# Roland_memser.net
KiCad netlist of a schematic drawn in EAGLE
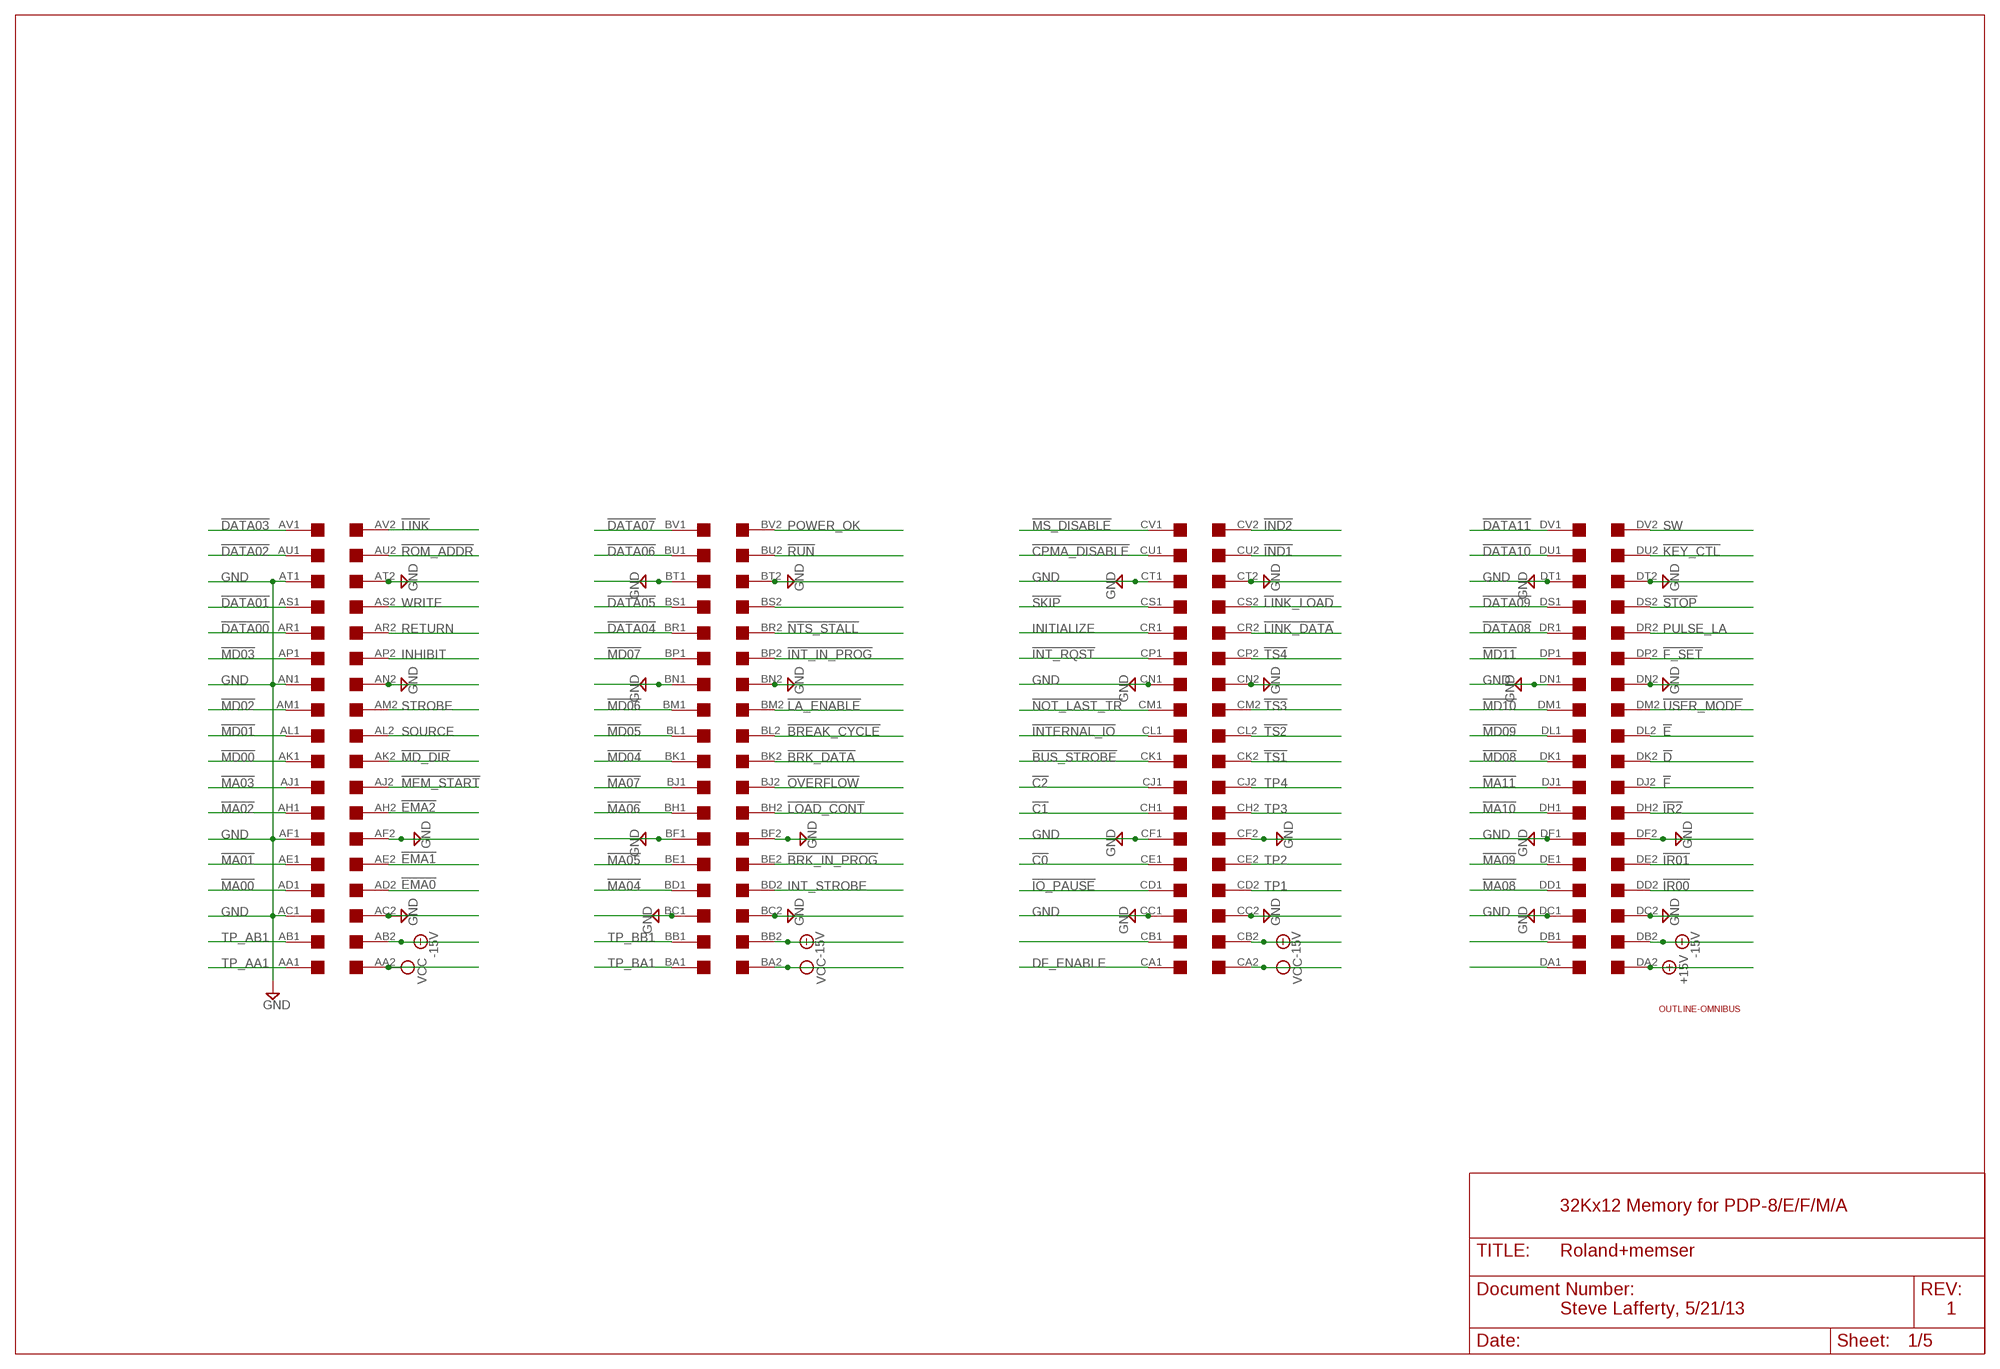
[diagram p0: schematic, sheet 1]
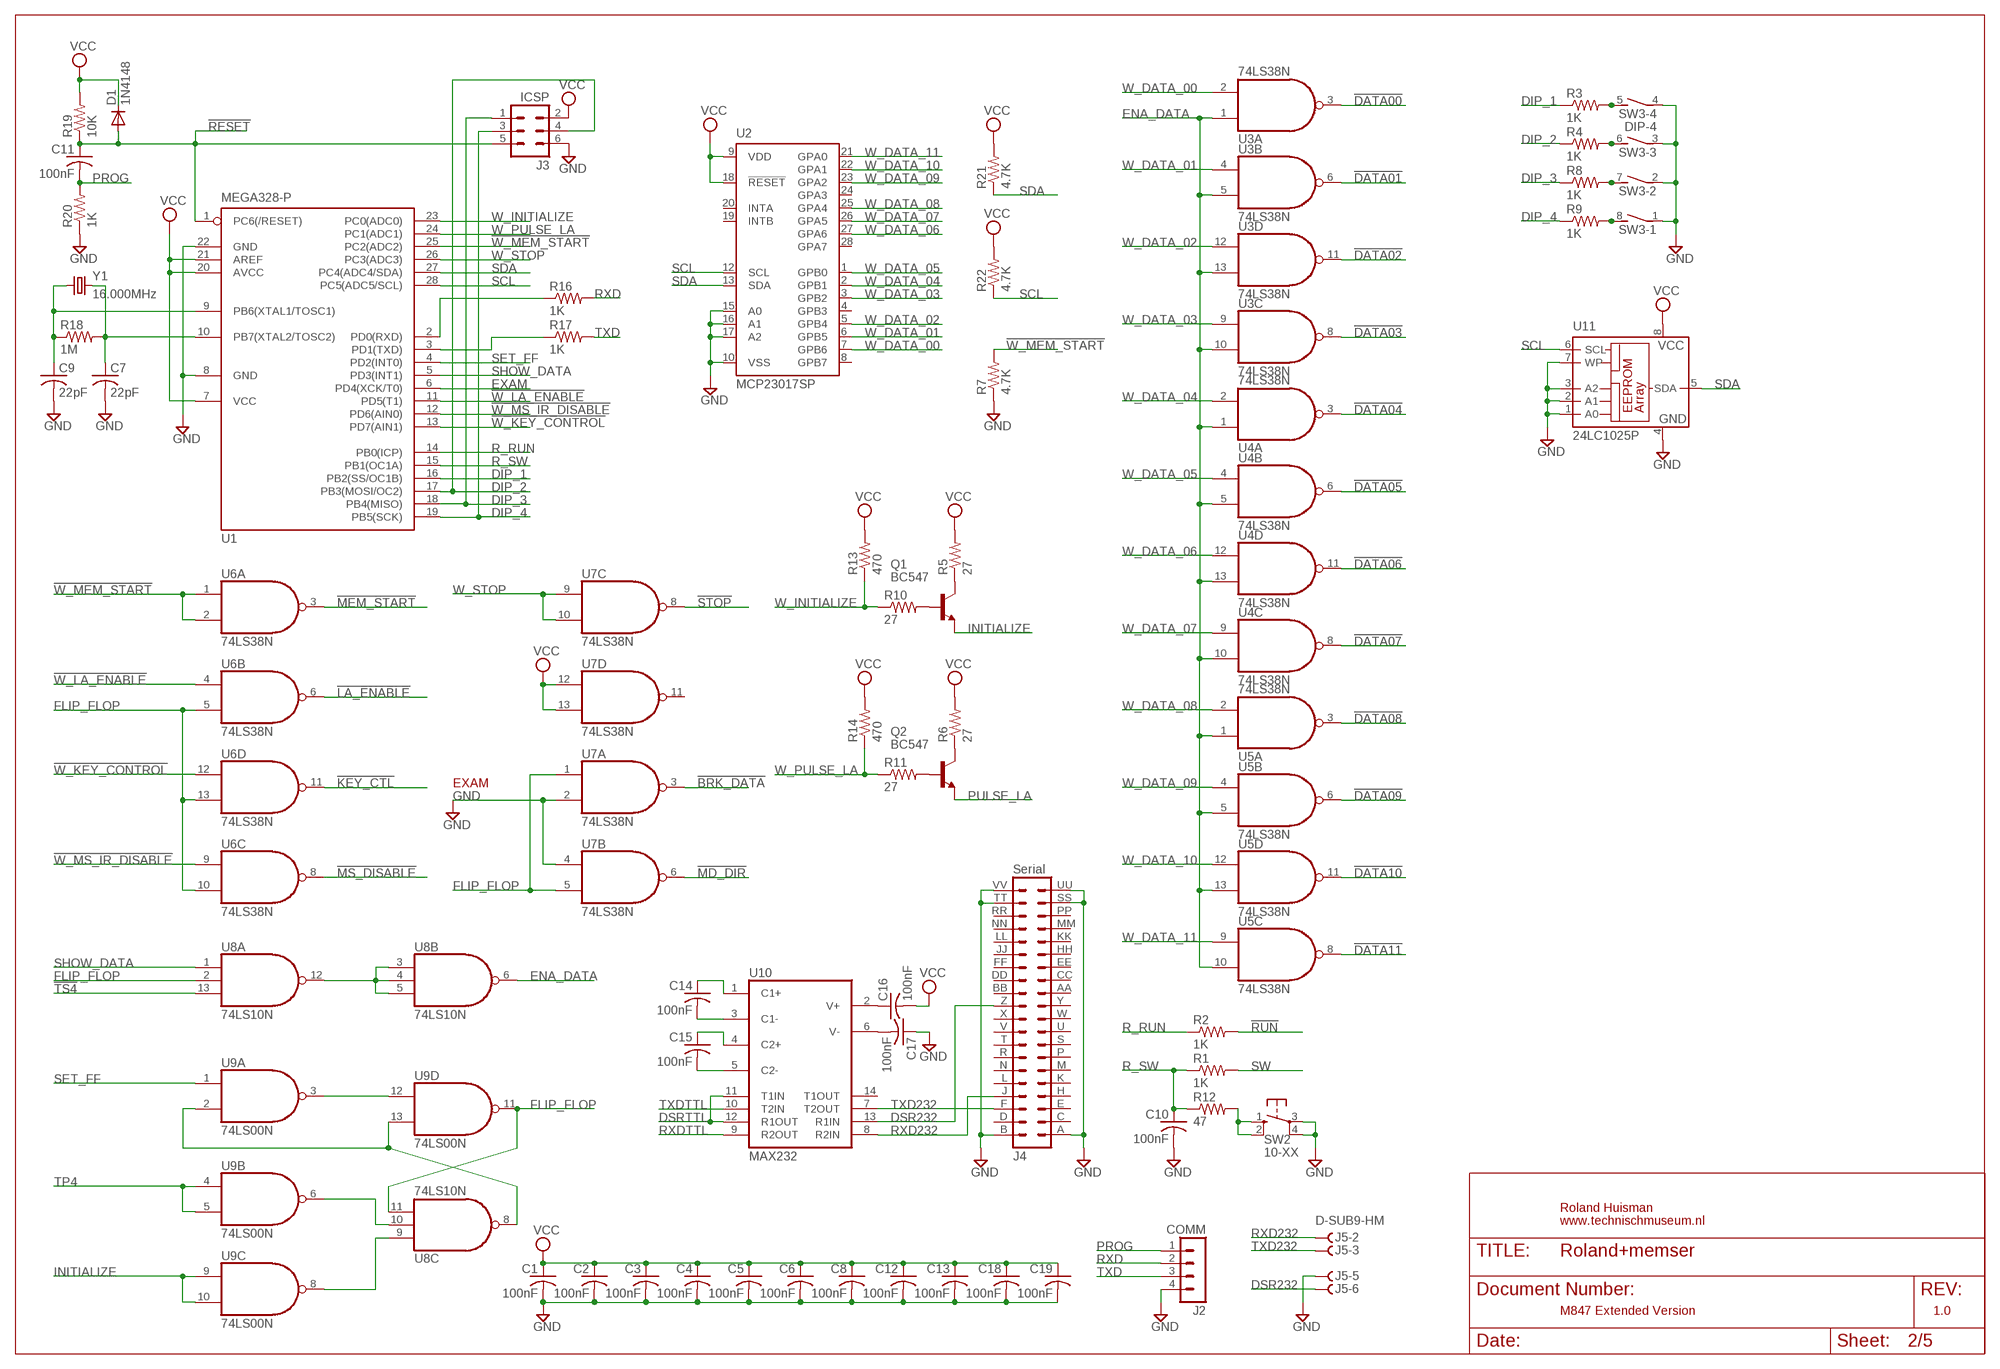
[diagram p1: schematic, sheet 2]
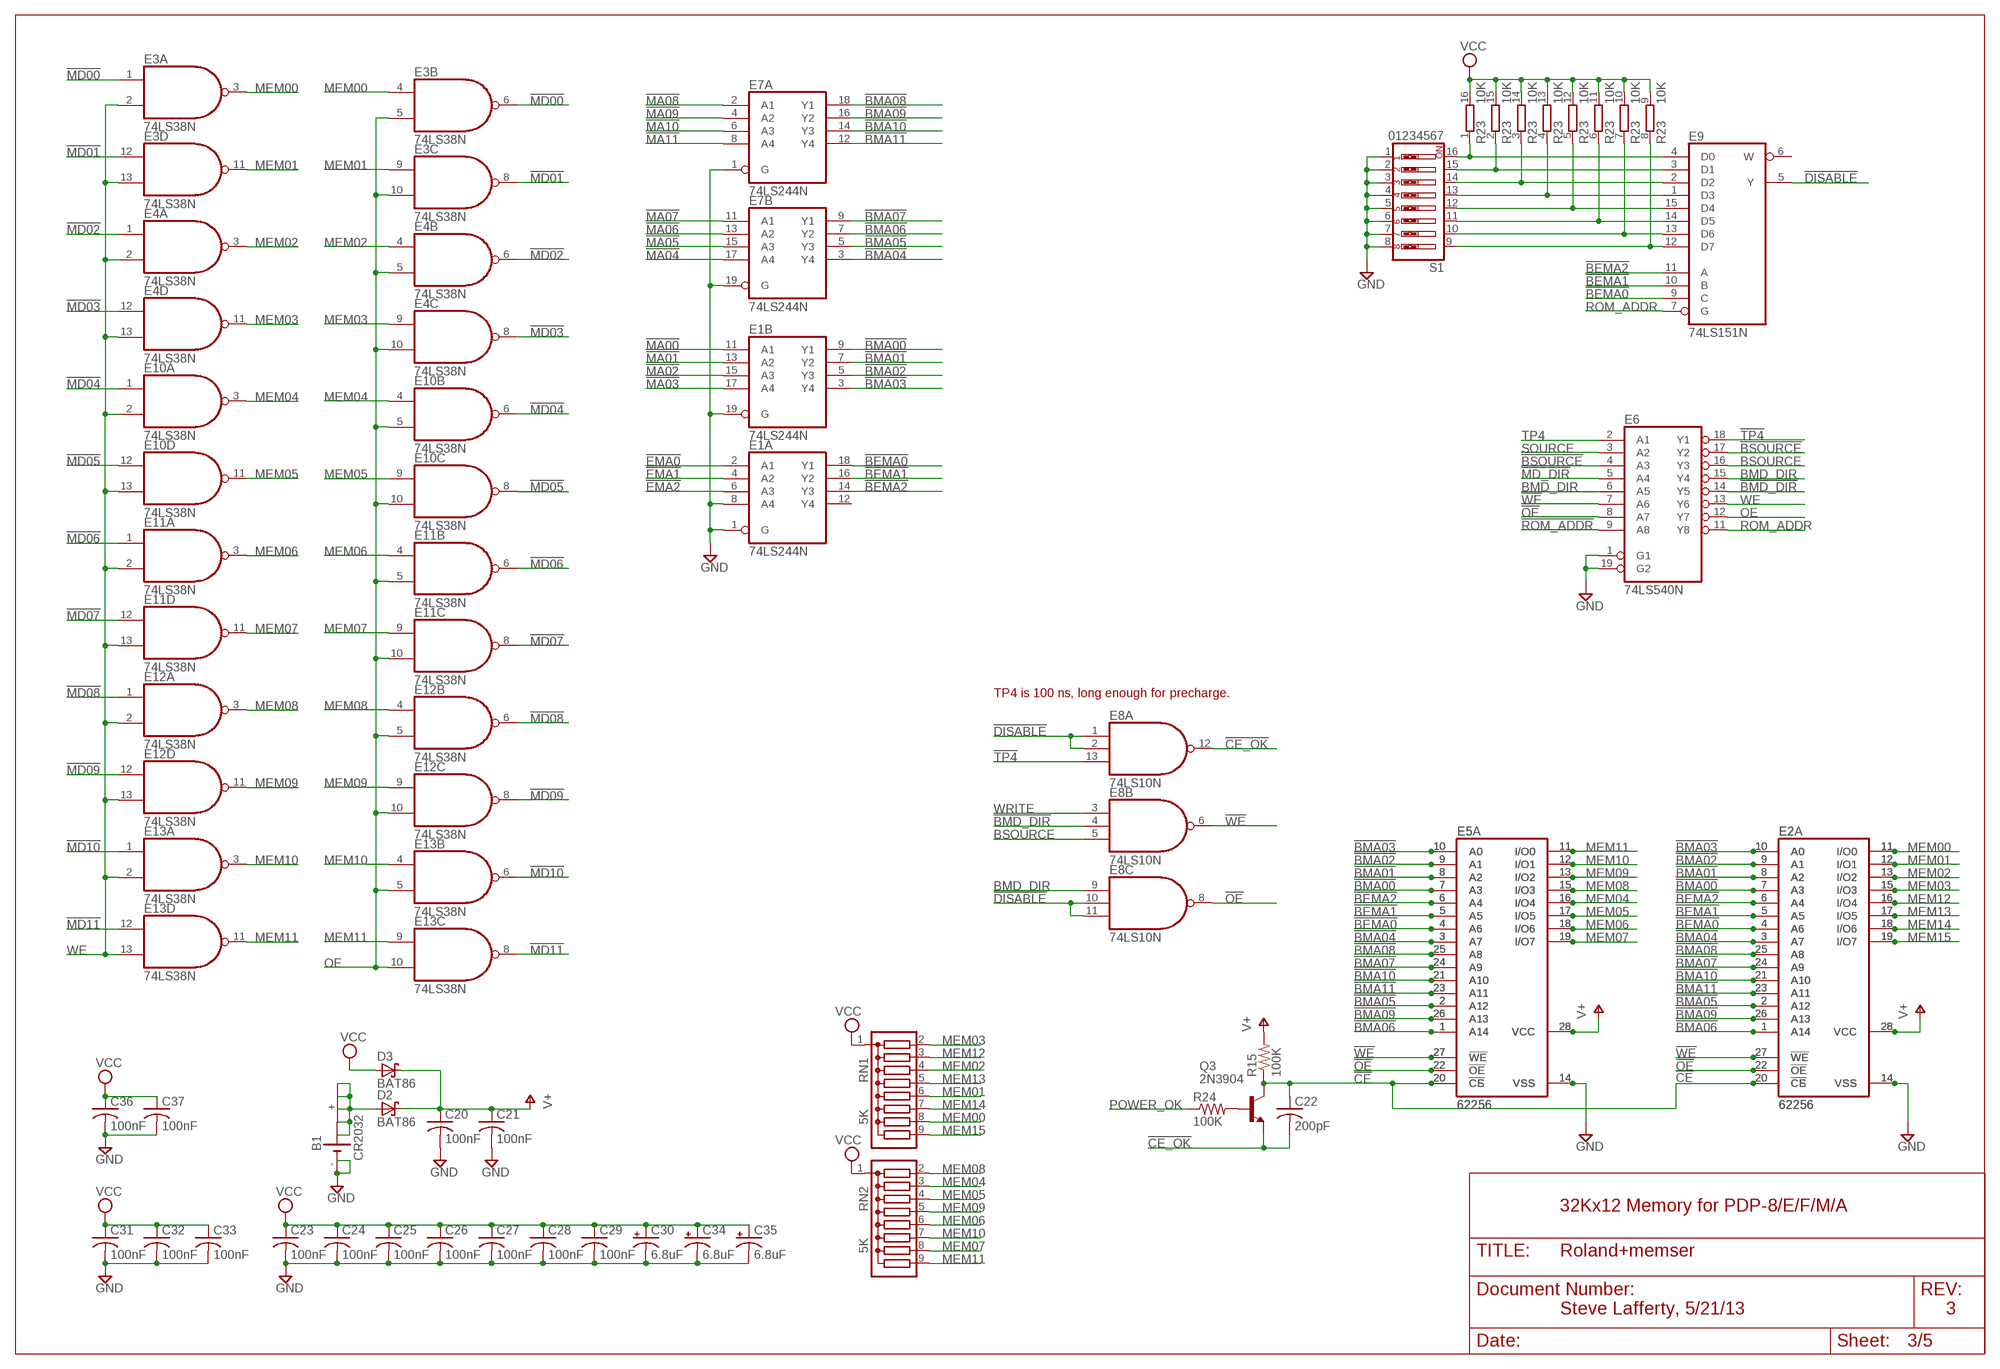
[diagram p2: schematic, sheet 3]
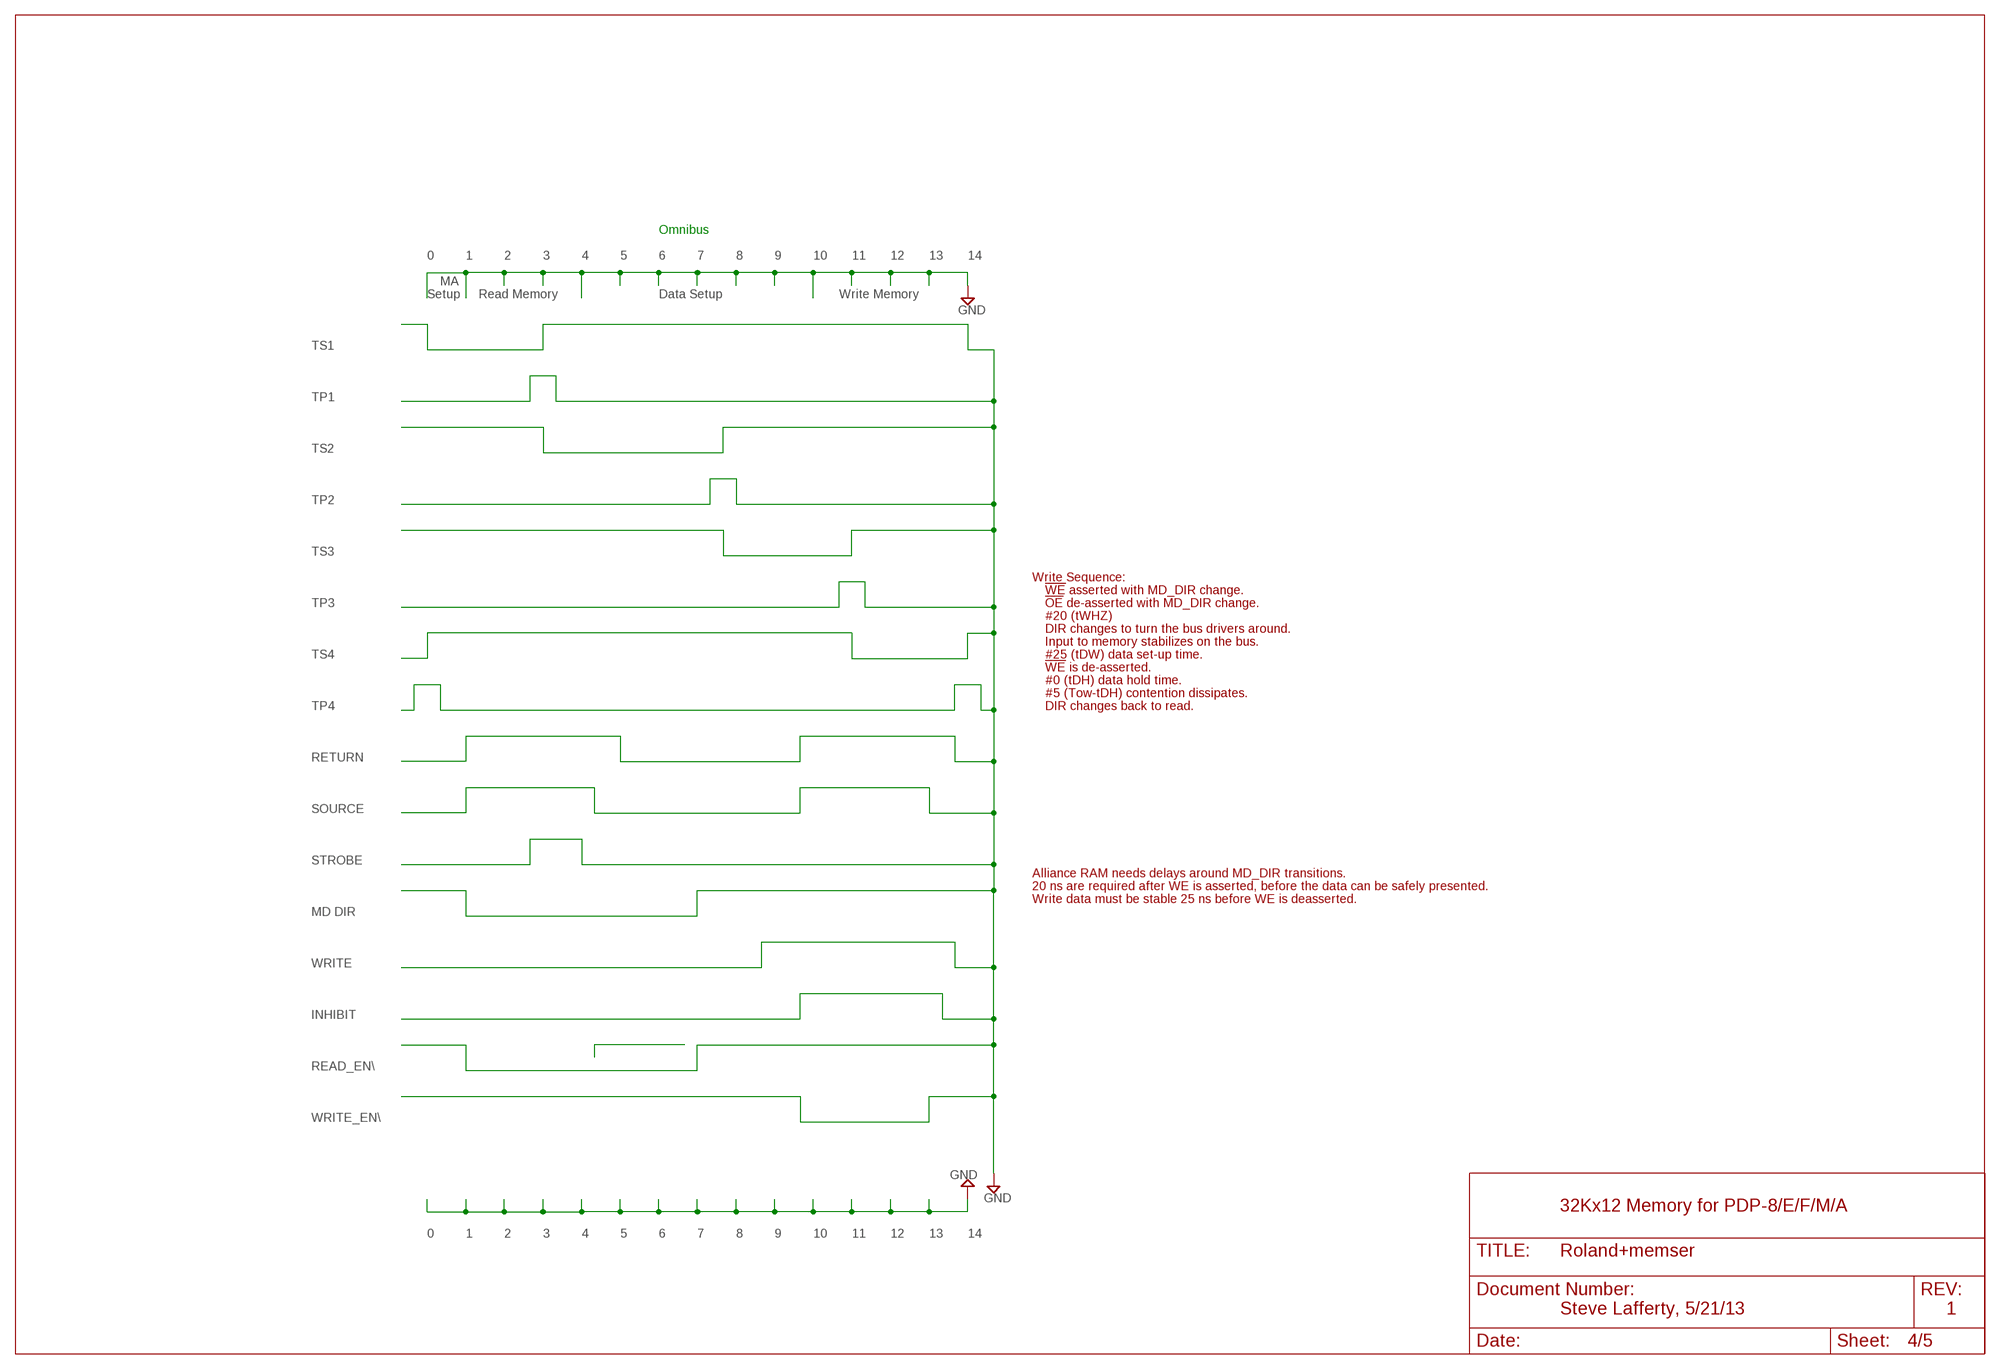
[diagram p3: schematic, sheet 4]
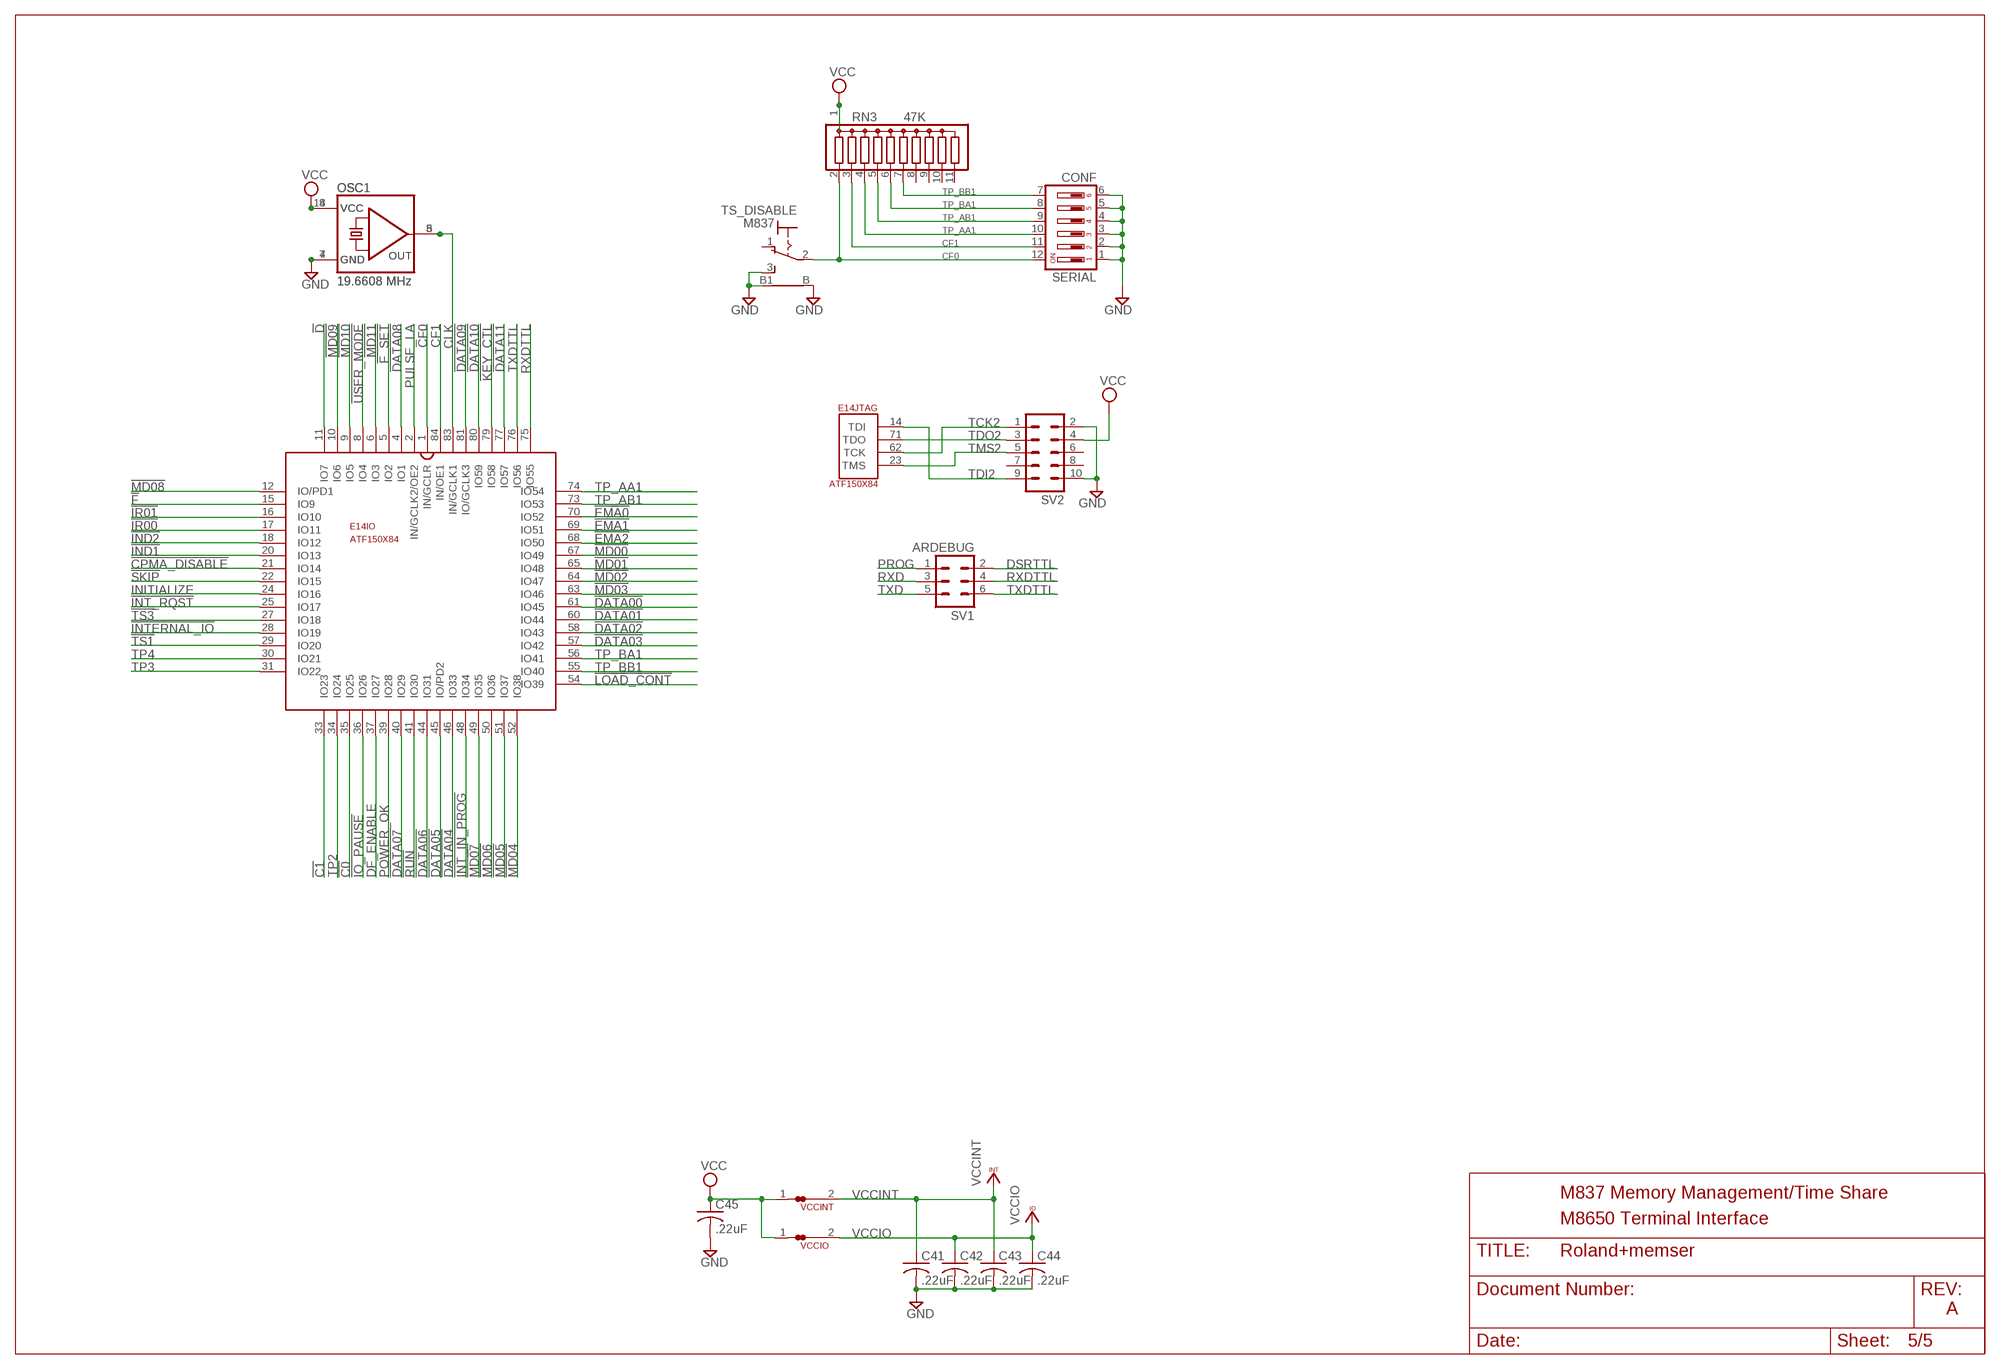
[diagram p4: schematic, sheet 5]

(export (version "E")
  (design (tool "Eeschema 10.0.6"))
  (components
    (comp (ref "J1")
      (value "EDGE")
      (footprint "eagle-import:EDGE-CON8")
      (libsource (lib "eagle-import") (part "QUAD"))
    )
    (comp (ref "U$1")
      (value "OUTLINE-OMNIBUS")
      (footprint "eagle-import:OMNIBUS")
      (libsource (lib "eagle-import") (part "OUTLINE-OMNIBUS"))
    )
    (comp (ref "C1")
      (value "100nF")
      (footprint "eagle-import:C050-025X075")
      (libsource (lib "eagle-import") (part "C-US050-025X075"))
    )
    (comp (ref "C2")
      (value "100nF")
      (footprint "eagle-import:C050-025X075")
      (libsource (lib "eagle-import") (part "C-US050-025X075"))
    )
    (comp (ref "C3")
      (value "100nF")
      (footprint "eagle-import:C050-025X075")
      (libsource (lib "eagle-import") (part "C-US050-025X075"))
    )
    (comp (ref "C4")
      (value "100nF")
      (footprint "eagle-import:C050-025X075")
      (libsource (lib "eagle-import") (part "C-US050-025X075"))
    )
    (comp (ref "C5")
      (value "100nF")
      (footprint "eagle-import:C050-025X075")
      (libsource (lib "eagle-import") (part "C-US050-025X075"))
    )
    (comp (ref "C6")
      (value "100nF")
      (footprint "eagle-import:C050-025X075")
      (libsource (lib "eagle-import") (part "C-US050-025X075"))
    )
    (comp (ref "C7")
      (value "22pF")
      (footprint "eagle-import:C050-025X075")
      (libsource (lib "eagle-import") (part "C-US050-025X075"))
    )
    (comp (ref "C8")
      (value "100nF")
      (footprint "eagle-import:C050-025X075")
      (libsource (lib "eagle-import") (part "C-US050-025X075"))
    )
    (comp (ref "C9")
      (value "22pF")
      (footprint "eagle-import:C050-025X075")
      (libsource (lib "eagle-import") (part "C-US050-025X075"))
    )
    (comp (ref "C10")
      (value "100nF")
      (footprint "eagle-import:C050-025X075")
      (libsource (lib "eagle-import") (part "C-US050-025X075"))
    )
    (comp (ref "C11")
      (value "100nF")
      (footprint "eagle-import:C050-025X075")
      (libsource (lib "eagle-import") (part "C-US050-025X075"))
    )
    (comp (ref "C12")
      (value "100nF")
      (footprint "eagle-import:C050-025X075")
      (libsource (lib "eagle-import") (part "C-US050-025X075"))
    )
    (comp (ref "C13")
      (value "100nF")
      (footprint "eagle-import:C050-025X075")
      (libsource (lib "eagle-import") (part "C-US050-025X075"))
    )
    (comp (ref "C14")
      (value "100nF")
      (footprint "eagle-import:C050-025X075")
      (libsource (lib "eagle-import") (part "C-US050-025X075"))
    )
    (comp (ref "C15")
      (value "100nF")
      (footprint "eagle-import:C050-025X075")
      (libsource (lib "eagle-import") (part "C-US050-025X075"))
    )
    (comp (ref "C16")
      (value "100nF")
      (footprint "eagle-import:C050-025X075")
      (libsource (lib "eagle-import") (part "C-US050-025X075"))
    )
    (comp (ref "C17")
      (value "100nF")
      (footprint "eagle-import:C050-025X075")
      (libsource (lib "eagle-import") (part "C-US050-025X075"))
    )
    (comp (ref "C18")
      (value "100nF")
      (footprint "eagle-import:C050-025X075")
      (libsource (lib "eagle-import") (part "C-US050-025X075"))
    )
    (comp (ref "C19")
      (value "100nF")
      (footprint "eagle-import:C050-025X075")
      (libsource (lib "eagle-import") (part "C-US050-025X075"))
    )
    (comp (ref "D1")
      (value "1N4148")
      (footprint "eagle-import:DO35-10")
      (libsource (lib "eagle-import") (part "1N4148DO35-10"))
    )
    (comp (ref "J2")
      (value "COMM")
      (footprint "eagle-import:MA04-1")
      (libsource (lib "eagle-import") (part "MA04-1"))
    )
    (comp (ref "J3")
      (value "ICSP")
      (footprint "eagle-import:MA03-2")
      (libsource (lib "eagle-import") (part "MA03-2"))
    )
    (comp (ref "J4")
      (value "Serial")
      (footprint "eagle-import:DEC40PINH")
      (libsource (lib "eagle-import") (part "DEC40PINH"))
    )
    (comp (ref "J5")
      (value "D-SUB9-HM")
      (footprint "eagle-import:H5M09RA")
      (libsource (lib "eagle-import") (part "D-SUB9-H5M09RA"))
    )
    (comp (ref "Q1")
      (value "BC547")
      (footprint "eagle-import:TO5")
      (libsource (lib "eagle-import") (part "-NPN-TO5"))
    )
    (comp (ref "Q2")
      (value "BC547")
      (footprint "eagle-import:TO5")
      (libsource (lib "eagle-import") (part "-NPN-TO5"))
    )
    (comp (ref "R1")
      (value "1K")
      (footprint "eagle-import:0207_10")
      (libsource (lib "eagle-import") (part "R-US_0207/10"))
    )
    (comp (ref "R2")
      (value "1K")
      (footprint "eagle-import:0207_10")
      (libsource (lib "eagle-import") (part "R-US_0207/10"))
    )
    (comp (ref "R3")
      (value "1K")
      (footprint "eagle-import:0207_10")
      (libsource (lib "eagle-import") (part "R-US_0207/10"))
    )
    (comp (ref "R4")
      (value "1K")
      (footprint "eagle-import:0207_10")
      (libsource (lib "eagle-import") (part "R-US_0207/10"))
    )
    (comp (ref "R5")
      (value "27")
      (footprint "eagle-import:0207_10")
      (libsource (lib "eagle-import") (part "R-US_0207/10"))
    )
    (comp (ref "R6")
      (value "27")
      (footprint "eagle-import:0207_10")
      (libsource (lib "eagle-import") (part "R-US_0207/10"))
    )
    (comp (ref "R7")
      (value "4.7K")
      (footprint "eagle-import:0207_10")
      (libsource (lib "eagle-import") (part "R-US_0207/10"))
    )
    (comp (ref "R8")
      (value "1K")
      (footprint "eagle-import:0207_10")
      (libsource (lib "eagle-import") (part "R-US_0207/10"))
    )
    (comp (ref "R9")
      (value "1K")
      (footprint "eagle-import:0207_10")
      (libsource (lib "eagle-import") (part "R-US_0207/10"))
    )
    (comp (ref "R10")
      (value "27")
      (footprint "eagle-import:0207_10")
      (libsource (lib "eagle-import") (part "R-US_0207/10"))
    )
    (comp (ref "R11")
      (value "27")
      (footprint "eagle-import:0207_10")
      (libsource (lib "eagle-import") (part "R-US_0207/10"))
    )
    (comp (ref "R12")
      (value "47")
      (footprint "eagle-import:0207_10")
      (libsource (lib "eagle-import") (part "R-US_0207/10"))
    )
    (comp (ref "R13")
      (value "470")
      (footprint "eagle-import:0207_10")
      (libsource (lib "eagle-import") (part "R-US_0207/10"))
    )
    (comp (ref "R14")
      (value "470")
      (footprint "eagle-import:0207_10")
      (libsource (lib "eagle-import") (part "R-US_0207/10"))
    )
    (comp (ref "R16")
      (value "1K")
      (footprint "eagle-import:0207_10")
      (libsource (lib "eagle-import") (part "R-US_0207/10"))
    )
    (comp (ref "R17")
      (value "1K")
      (footprint "eagle-import:0207_10")
      (libsource (lib "eagle-import") (part "R-US_0207/10"))
    )
    (comp (ref "R18")
      (value "1M")
      (footprint "eagle-import:0207_10")
      (libsource (lib "eagle-import") (part "R-US_0207/10"))
    )
    (comp (ref "R19")
      (value "10K")
      (footprint "eagle-import:0207_10")
      (libsource (lib "eagle-import") (part "R-US_0207/10"))
    )
    (comp (ref "R20")
      (value "1K")
      (footprint "eagle-import:0207_10")
      (libsource (lib "eagle-import") (part "R-US_0207/10"))
    )
    (comp (ref "R21")
      (value "4.7K")
      (footprint "eagle-import:0207_10")
      (libsource (lib "eagle-import") (part "R-US_0207/10"))
    )
    (comp (ref "R22")
      (value "4.7K")
      (footprint "eagle-import:0207_10")
      (libsource (lib "eagle-import") (part "R-US_0207/10"))
    )
    (comp (ref "SW2")
      (value "10-XX")
      (footprint "eagle-import:B3F-10XX")
      (fields (field (name "MPN") "B3F-1000"))
      (libsource (lib "eagle-import") (part "10-XX"))
    )
    (comp (ref "SW3")
      (value "DIP-4")
      (footprint "eagle-import:DIP04S")
      (libsource (lib "eagle-import") (part "DIP04S"))
    )
    (comp (ref "U1")
      (value "MEGA328-P")
      (footprint "eagle-import:DIL28-3")
      (libsource (lib "eagle-import") (part "MEGA8-P"))
    )
    (comp (ref "U2")
      (value "MCP23017SP")
      (footprint "eagle-import:DIL28-3")
      (fields (field (name "MF") "MICROCHIP") (field (name "MPN") "MCP23017-E/SP"))
      (libsource (lib "eagle-import") (part "MCP23017SP"))
    )
    (comp (ref "U3")
      (value "74LS38N")
      (footprint "eagle-import:DIL14")
      (libsource (lib "eagle-import") (part "7438NLS"))
    )
    (comp (ref "U4")
      (value "74LS38N")
      (footprint "eagle-import:DIL14")
      (libsource (lib "eagle-import") (part "7438NLS"))
    )
    (comp (ref "U5")
      (value "74LS38N")
      (footprint "eagle-import:DIL14")
      (libsource (lib "eagle-import") (part "7438NLS"))
    )
    (comp (ref "U6")
      (value "74LS38N")
      (footprint "eagle-import:DIL14")
      (libsource (lib "eagle-import") (part "7438NLS"))
    )
    (comp (ref "U7")
      (value "74LS38N")
      (footprint "eagle-import:DIL14")
      (libsource (lib "eagle-import") (part "7438NLS"))
    )
    (comp (ref "U8")
      (value "74LS10N")
      (footprint "eagle-import:DIL14")
      (libsource (lib "eagle-import") (part "7410NLS"))
    )
    (comp (ref "U9")
      (value "74LS00N")
      (footprint "eagle-import:DIL14")
      (libsource (lib "eagle-import") (part "7400NLS"))
    )
    (comp (ref "U10")
      (value "MAX232")
      (footprint "eagle-import:DIL16")
      (fields (field (name "MF") "MAXIM") (field (name "MPN") "MAX232ACPE+"))
      (libsource (lib "eagle-import") (part "MAX232"))
    )
    (comp (ref "U11")
      (value "24LC1025P")
      (footprint "eagle-import:DIL8")
      (fields (field (name "MF") "MICROCHIP") (field (name "MPN") "24LC025-I/P"))
      (libsource (lib "eagle-import") (part "24PLC025"))
    )
    (comp (ref "Y1")
      (value "16.000MHz")
      (footprint "eagle-import:HC49U-H")
      (libsource (lib "eagle-import") (part "CRYSTALHC49U-H"))
    )
    (comp (ref "C41")
      (value ".22uF")
      (footprint "eagle-import:C063-025X075")
      (libsource (lib "eagle-import") (part "C-US"))
    )
    (comp (ref "C42")
      (value ".22uF")
      (footprint "eagle-import:C063-025X075")
      (libsource (lib "eagle-import") (part "C-US"))
    )
    (comp (ref "C43")
      (value ".22uF")
      (footprint "eagle-import:C063-025X075")
      (libsource (lib "eagle-import") (part "C-US"))
    )
    (comp (ref "C44")
      (value ".22uF")
      (footprint "eagle-import:C063-025X075")
      (libsource (lib "eagle-import") (part "C-US"))
    )
    (comp (ref "C45")
      (value ".22uF")
      (footprint "eagle-import:C063-025X075")
      (libsource (lib "eagle-import") (part "C-US"))
    )
    (comp (ref "E14")
      (value "ATF150X84")
      (footprint "eagle-import:S84")
      (libsource (lib "eagle-import") (part "ATF150X84"))
    )
    (comp (ref "OSC")
      (value "19.6608 MHz")
      (footprint "eagle-import:DIL08S")
      (libsource (lib "eagle-import") (part "QG5460"))
    )
    (comp (ref "OSC1")
      (value "19.6608 MHz")
      (footprint "eagle-import:DIL14S")
      (libsource (lib "eagle-import") (part "QG5860"))
    )
    (comp (ref "RN3")
      (value "47K")
      (footprint "eagle-import:SIL11")
      (libsource (lib "eagle-import") (part "G10R"))
    )
    (comp (ref "SERIAL")
      (value "CONF")
      (footprint "eagle-import:DP-06")
      (fields (field (name "MPN") "MCDP06"))
      (libsource (lib "eagle-import") (part "DP06"))
    )
    (comp (ref "SV1")
      (value "ARDEBUG")
      (footprint "eagle-import:MA03-2")
      (libsource (lib "eagle-import") (part "MA03-2"))
    )
    (comp (ref "SV2")
      (value "ML10")
      (footprint "eagle-import:ML10")
      (libsource (lib "eagle-import") (part "ML10"))
    )
    (comp (ref "TS_DISABLE")
      (value "M837")
      (footprint "eagle-import:9070-1W")
      (libsource (lib "eagle-import") (part "9070-1W"))
    )
    (comp (ref "VCCINT")
      (value "JUMPER-NC1")
      (footprint "eagle-import:NC1")
      (libsource (lib "eagle-import") (part "JUMPER-NC1"))
    )
    (comp (ref "VCCIO")
      (value "JUMPER-NC1")
      (footprint "eagle-import:NC1")
      (libsource (lib "eagle-import") (part "JUMPER-NC1"))
    )
    (comp (ref "B1")
      (value "CR2032")
      (footprint "eagle-import:B2430UNI")
      (libsource (lib "eagle-import") (part "B2430UNI"))
    )
    (comp (ref "C20")
      (value "100nF")
      (footprint "eagle-import:C050-025X075")
      (libsource (lib "eagle-import") (part "C-US050-025X075"))
    )
    (comp (ref "C21")
      (value "100nF")
      (footprint "eagle-import:C050-025X075")
      (libsource (lib "eagle-import") (part "C-US050-025X075"))
    )
    (comp (ref "C22")
      (value "200pF")
      (footprint "eagle-import:C050-025X075")
      (libsource (lib "eagle-import") (part "C-US050-025X075"))
    )
    (comp (ref "C23")
      (value "100nF")
      (footprint "eagle-import:C050-025X075")
      (libsource (lib "eagle-import") (part "C-US050-025X075"))
    )
    (comp (ref "C24")
      (value "100nF")
      (footprint "eagle-import:C050-025X075")
      (libsource (lib "eagle-import") (part "C-US050-025X075"))
    )
    (comp (ref "C25")
      (value "100nF")
      (footprint "eagle-import:C050-025X075")
      (libsource (lib "eagle-import") (part "C-US050-025X075"))
    )
    (comp (ref "C26")
      (value "100nF")
      (footprint "eagle-import:C050-025X075")
      (libsource (lib "eagle-import") (part "C-US050-025X075"))
    )
    (comp (ref "C27")
      (value "100nF")
      (footprint "eagle-import:C050-025X075")
      (libsource (lib "eagle-import") (part "C-US050-025X075"))
    )
    (comp (ref "C28")
      (value "100nF")
      (footprint "eagle-import:C050-025X075")
      (libsource (lib "eagle-import") (part "C-US050-025X075"))
    )
    (comp (ref "C29")
      (value "100nF")
      (footprint "eagle-import:C050-025X075")
      (libsource (lib "eagle-import") (part "C-US050-025X075"))
    )
    (comp (ref "C30")
      (value "6.8uF")
      (footprint "eagle-import:E12-8")
      (libsource (lib "eagle-import") (part "CPOL-USE20-8AXIAL"))
    )
    (comp (ref "C31")
      (value "100nF")
      (footprint "eagle-import:C050-025X075")
      (libsource (lib "eagle-import") (part "C-US050-025X075"))
    )
    (comp (ref "C32")
      (value "100nF")
      (footprint "eagle-import:C050-025X075")
      (libsource (lib "eagle-import") (part "C-US050-025X075"))
    )
    (comp (ref "C33")
      (value "100nF")
      (footprint "eagle-import:C050-025X075")
      (libsource (lib "eagle-import") (part "C-US050-025X075"))
    )
    (comp (ref "C34")
      (value "6.8uF")
      (footprint "eagle-import:E12-8")
      (libsource (lib "eagle-import") (part "CPOL-USE20-8AXIAL"))
    )
    (comp (ref "C35")
      (value "6.8uF")
      (footprint "eagle-import:E12-8")
      (libsource (lib "eagle-import") (part "CPOL-USE20-8AXIAL"))
    )
    (comp (ref "C36")
      (value "100nF")
      (footprint "eagle-import:C050-025X075")
      (libsource (lib "eagle-import") (part "C-US050-025X075"))
    )
    (comp (ref "C37")
      (value "100nF")
      (footprint "eagle-import:C050-025X075")
      (libsource (lib "eagle-import") (part "C-US050-025X075"))
    )
    (comp (ref "D2")
      (value "BAT86")
      (footprint "eagle-import:DO35-10")
      (libsource (lib "eagle-import") (part "BAT19"))
    )
    (comp (ref "D3")
      (value "BAT86")
      (footprint "eagle-import:DO35-10")
      (libsource (lib "eagle-import") (part "BAT19"))
    )
    (comp (ref "E1")
      (value "74LS244N")
      (footprint "eagle-import:DIL20")
      (libsource (lib "eagle-import") (part "74244NLS"))
    )
    (comp (ref "E2")
      (value "62256")
      (footprint "eagle-import:DIL28-6")
      (libsource (lib "eagle-import") (part "58C256P"))
    )
    (comp (ref "E2A")
      (value "62256")
      (footprint "eagle-import:DIL28-3")
      (libsource (lib "eagle-import") (part "62832P"))
    )
    (comp (ref "E3")
      (value "74LS38N")
      (footprint "eagle-import:DIL14")
      (libsource (lib "eagle-import") (part "7438NLS"))
    )
    (comp (ref "E4")
      (value "74LS38N")
      (footprint "eagle-import:DIL14")
      (libsource (lib "eagle-import") (part "7438NLS"))
    )
    (comp (ref "E5")
      (value "62256")
      (footprint "eagle-import:DIL28-6")
      (libsource (lib "eagle-import") (part "58C256P"))
    )
    (comp (ref "E5A")
      (value "62256")
      (footprint "eagle-import:DIL28-3")
      (libsource (lib "eagle-import") (part "62832P"))
    )
    (comp (ref "E6")
      (value "74LS540N")
      (footprint "eagle-import:DIL20")
      (libsource (lib "eagle-import") (part "74540NLS"))
    )
    (comp (ref "E7")
      (value "74LS244N")
      (footprint "eagle-import:DIL20")
      (libsource (lib "eagle-import") (part "74244NLS"))
    )
    (comp (ref "E8")
      (value "74LS10N")
      (footprint "eagle-import:DIL14")
      (libsource (lib "eagle-import") (part "7410NLS"))
    )
    (comp (ref "E9")
      (value "74LS151N")
      (footprint "eagle-import:DIL16")
      (libsource (lib "eagle-import") (part "74151NLS"))
    )
    (comp (ref "E10")
      (value "74LS38N")
      (footprint "eagle-import:DIL14")
      (libsource (lib "eagle-import") (part "7438NLS"))
    )
    (comp (ref "E11")
      (value "74LS38N")
      (footprint "eagle-import:DIL14")
      (libsource (lib "eagle-import") (part "7438NLS"))
    )
    (comp (ref "E12")
      (value "74LS38N")
      (footprint "eagle-import:DIL14")
      (libsource (lib "eagle-import") (part "7438NLS"))
    )
    (comp (ref "E13")
      (value "74LS38N")
      (footprint "eagle-import:DIL14")
      (libsource (lib "eagle-import") (part "7438NLS"))
    )
    (comp (ref "Q3")
      (value "2N3904")
      (footprint "eagle-import:TO92")
      (libsource (lib "eagle-import") (part "2N3904"))
    )
    (comp (ref "R15")
      (value "100K")
      (footprint "eagle-import:0207_10")
      (libsource (lib "eagle-import") (part "R-US_0207/10"))
    )
    (comp (ref "R23")
      (value "10K")
      (footprint "eagle-import:DIL16")
      (libsource (lib "eagle-import") (part "8R-P"))
    )
    (comp (ref "R24")
      (value "100K")
      (footprint "eagle-import:0207_10")
      (libsource (lib "eagle-import") (part "R-US_0207/10"))
    )
    (comp (ref "RN1")
      (value "5K")
      (footprint "eagle-import:SIL9")
      (libsource (lib "eagle-import") (part "G08R"))
    )
    (comp (ref "RN2")
      (value "5K")
      (footprint "eagle-import:SIL9")
      (libsource (lib "eagle-import") (part "G08R"))
    )
    (comp (ref "S1")
      (value "01234567")
      (footprint "eagle-import:EDG-08")
      (libsource (lib "eagle-import") (part "SW_DIP-8"))
    )
  )
  (nets
    (net (code "1") (name "+15V") (class "Default")
      (node (ref "J1") (pin "DA2") (pinfunction "1_DA2") (pintype "bidirectional"))
    )
    (net (code "2") (name "-15V") (class "Default")
      (node (ref "J1") (pin "AB2") (pinfunction "1_AB2") (pintype "bidirectional"))
      (node (ref "J1") (pin "BB2") (pinfunction "1_BB2") (pintype "bidirectional"))
      (node (ref "J1") (pin "CB2") (pinfunction "1_CB2") (pintype "bidirectional"))
      (node (ref "J1") (pin "DB2") (pinfunction "1_DB2") (pintype "bidirectional"))
    )
    (net (code "3") (name "BMD_DIR") (class "Default")
      (node (ref "E6") (pin "15") (pinfunction "Y4_15") (pintype "tri_state"))
      (node (ref "E6") (pin "6") (pinfunction "A5_6") (pintype "input"))
      (node (ref "E8") (pin "9") (pinfunction "I0_9") (pintype "input"))
    )
    (net (code "4") (name "BSOURCE") (class "Default")
      (node (ref "E6") (pin "16") (pinfunction "Y3_16") (pintype "tri_state"))
      (node (ref "E8") (pin "5") (pinfunction "I2_5") (pintype "input"))
    )
    (net (code "5") (name "CF0") (class "Default")
      (node (ref "E14") (pin "1") (pinfunction "IN/GCLR_1") (pintype "input"))
      (node (ref "RN3") (pin "2") (pinfunction "2_2") (pintype "passive"))
      (node (ref "SERIAL") (pin "12") (pinfunction "12_12") (pintype "passive"))
      (node (ref "TS_DISABLE") (pin "2") (pinfunction "P_2") (pintype "passive"))
    )
    (net (code "6") (name "CF1") (class "Default")
      (node (ref "E14") (pin "84") (pinfunction "IN/OE1_84") (pintype "input"))
      (node (ref "RN3") (pin "3") (pinfunction "3_3") (pintype "passive"))
      (node (ref "SERIAL") (pin "11") (pinfunction "11_11") (pintype "passive"))
    )
    (net (code "7") (name "CLK") (class "Default")
      (node (ref "E14") (pin "83") (pinfunction "IN/GCLK1_83") (pintype "input"))
      (node (ref "OSC") (pin "5") (pinfunction "OUT_5") (pintype "output"))
      (node (ref "OSC1") (pin "8") (pinfunction "OUT_8") (pintype "output"))
    )
    (net (code "8") (name "DF_ENABLE") (class "Default")
      (node (ref "E14") (pin "37") (pinfunction "IO27_37") (pintype "bidirectional"))
      (node (ref "J1") (pin "CA1") (pinfunction "1_CA1") (pintype "bidirectional"))
    )
    (net (code "9") (name "DIP_1") (class "Default")
      (node (ref "R3") (pin "1") (pinfunction "1_1") (pintype "passive"))
      (node (ref "U1") (pin "16") (pinfunction "PB2(SS/OC1B)_16") (pintype "bidirectional"))
    )
    (net (code "10") (name "DIP_2") (class "Default")
      (node (ref "J3") (pin "4") (pinfunction "4_4") (pintype "passive"))
      (node (ref "R4") (pin "1") (pinfunction "1_1") (pintype "passive"))
      (node (ref "U1") (pin "17") (pinfunction "PB3(MOSI/OC2)_17") (pintype "bidirectional"))
    )
    (net (code "11") (name "DIP_3") (class "Default")
      (node (ref "J3") (pin "1") (pinfunction "1_1") (pintype "passive"))
      (node (ref "R8") (pin "1") (pinfunction "1_1") (pintype "passive"))
      (node (ref "U1") (pin "18") (pinfunction "PB4(MISO)_18") (pintype "bidirectional"))
    )
    (net (code "12") (name "DIP_4") (class "Default")
      (node (ref "J3") (pin "3") (pinfunction "3_3") (pintype "passive"))
      (node (ref "R9") (pin "1") (pinfunction "1_1") (pintype "passive"))
      (node (ref "U1") (pin "19") (pinfunction "PB5(SCK)_19") (pintype "bidirectional"))
    )
    (net (code "13") (name "DSR232") (class "Default")
      (node (ref "J4") (pin "Z") (pinfunction "22_Z") (pintype "bidirectional"))
      (node (ref "J5") (pin "6") (pinfunction "F_6") (pintype "passive"))
      (node (ref "U10") (pin "13") (pinfunction "R1IN_13") (pintype "input"))
    )
    (net (code "14") (name "DSRTTL") (class "Default")
      (node (ref "SV1") (pin "2") (pinfunction "2_2") (pintype "passive"))
      (node (ref "U10") (pin "11") (pinfunction "T1IN_11") (pintype "input"))
      (node (ref "U10") (pin "12") (pinfunction "R1OUT_12") (pintype "output"))
    )
    (net (code "15") (name "ENA_DATA") (class "Default")
      (node (ref "U3") (pin "1") (pinfunction "I0_1") (pintype "input"))
      (node (ref "U3") (pin "10") (pinfunction "I1_10") (pintype "input"))
      (node (ref "U3") (pin "13") (pinfunction "I1_13") (pintype "input"))
      (node (ref "U3") (pin "5") (pinfunction "I1_5") (pintype "input"))
      (node (ref "U4") (pin "1") (pinfunction "I0_1") (pintype "input"))
      (node (ref "U4") (pin "10") (pinfunction "I1_10") (pintype "input"))
      (node (ref "U4") (pin "13") (pinfunction "I1_13") (pintype "input"))
      (node (ref "U4") (pin "5") (pinfunction "I1_5") (pintype "input"))
      (node (ref "U5") (pin "1") (pinfunction "I0_1") (pintype "input"))
      (node (ref "U5") (pin "10") (pinfunction "I1_10") (pintype "input"))
      (node (ref "U5") (pin "13") (pinfunction "I1_13") (pintype "input"))
      (node (ref "U5") (pin "5") (pinfunction "I1_5") (pintype "input"))
      (node (ref "U8") (pin "6") (pinfunction "O_6") (pintype "output"))
    )
    (net (code "16") (name "EXAM") (class "Default")
      (node (ref "U1") (pin "6") (pinfunction "PD4(XCK/T0)_6") (pintype "bidirectional"))
    )
    (net (code "17") (name "FLIP_FLOP") (class "Default")
      (node (ref "U6") (pin "10") (pinfunction "I1_10") (pintype "input"))
      (node (ref "U6") (pin "13") (pinfunction "I1_13") (pintype "input"))
      (node (ref "U6") (pin "5") (pinfunction "I1_5") (pintype "input"))
      (node (ref "U7") (pin "1") (pinfunction "I0_1") (pintype "input"))
      (node (ref "U7") (pin "5") (pinfunction "I1_5") (pintype "input"))
      (node (ref "U8") (pin "11") (pinfunction "I2_11") (pintype "input"))
      (node (ref "U8") (pin "2") (pinfunction "I1_2") (pintype "input"))
      (node (ref "U9") (pin "11") (pinfunction "O_11") (pintype "output"))
    )
    (net (code "18") (name "GND") (class "Default")
      (node (ref "B1") (pin "-") (pinfunction "-_-") (pintype "passive"))
      (node (ref "B1") (pin "-@1") (pinfunction "-_-@1") (pintype "passive"))
      (node (ref "C1") (pin "2") (pinfunction "2_2") (pintype "passive"))
      (node (ref "C10") (pin "2") (pinfunction "2_2") (pintype "passive"))
      (node (ref "C12") (pin "2") (pinfunction "2_2") (pintype "passive"))
      (node (ref "C13") (pin "2") (pinfunction "2_2") (pintype "passive"))
      (node (ref "C17") (pin "1") (pinfunction "1_1") (pintype "passive"))
      (node (ref "C18") (pin "2") (pinfunction "2_2") (pintype "passive"))
      (node (ref "C19") (pin "2") (pinfunction "2_2") (pintype "passive"))
      (node (ref "C2") (pin "2") (pinfunction "2_2") (pintype "passive"))
      (node (ref "C20") (pin "2") (pinfunction "2_2") (pintype "passive"))
      (node (ref "C21") (pin "2") (pinfunction "2_2") (pintype "passive"))
      (node (ref "C23") (pin "2") (pinfunction "2_2") (pintype "passive"))
      (node (ref "C24") (pin "2") (pinfunction "2_2") (pintype "passive"))
      (node (ref "C25") (pin "2") (pinfunction "2_2") (pintype "passive"))
      (node (ref "C26") (pin "2") (pinfunction "2_2") (pintype "passive"))
      (node (ref "C27") (pin "2") (pinfunction "2_2") (pintype "passive"))
      (node (ref "C28") (pin "2") (pinfunction "2_2") (pintype "passive"))
      (node (ref "C29") (pin "2") (pinfunction "2_2") (pintype "passive"))
      (node (ref "C3") (pin "2") (pinfunction "2_2") (pintype "passive"))
      (node (ref "C30") (pin "-") (pinfunction "-_-") (pintype "passive"))
      (node (ref "C31") (pin "2") (pinfunction "2_2") (pintype "passive"))
      (node (ref "C32") (pin "2") (pinfunction "2_2") (pintype "passive"))
      (node (ref "C33") (pin "2") (pinfunction "2_2") (pintype "passive"))
      (node (ref "C34") (pin "-") (pinfunction "-_-") (pintype "passive"))
      (node (ref "C35") (pin "-") (pinfunction "-_-") (pintype "passive"))
      (node (ref "C36") (pin "2") (pinfunction "2_2") (pintype "passive"))
      (node (ref "C37") (pin "2") (pinfunction "2_2") (pintype "passive"))
      (node (ref "C4") (pin "2") (pinfunction "2_2") (pintype "passive"))
      (node (ref "C41") (pin "2") (pinfunction "2_2") (pintype "passive"))
      (node (ref "C42") (pin "2") (pinfunction "2_2") (pintype "passive"))
      (node (ref "C43") (pin "2") (pinfunction "2_2") (pintype "passive"))
      (node (ref "C44") (pin "2") (pinfunction "2_2") (pintype "passive"))
      (node (ref "C45") (pin "2") (pinfunction "2_2") (pintype "passive"))
      (node (ref "C5") (pin "2") (pinfunction "2_2") (pintype "passive"))
      (node (ref "C6") (pin "2") (pinfunction "2_2") (pintype "passive"))
      (node (ref "C7") (pin "2") (pinfunction "2_2") (pintype "passive"))
      (node (ref "C8") (pin "2") (pinfunction "2_2") (pintype "passive"))
      (node (ref "C9") (pin "2") (pinfunction "2_2") (pintype "passive"))
      (node (ref "E1") (pin "1") (pinfunction "G_1") (pintype "input"))
      (node (ref "E1") (pin "19") (pinfunction "G_19") (pintype "input"))
      (node (ref "E1") (pin "8") (pinfunction "A4_8") (pintype "input"))
      (node (ref "E2") (pin "14") (pinfunction "VSS_14") (pintype "power_in"))
      (node (ref "E2A") (pin "14") (pinfunction "VSS_14") (pintype "power_in"))
      (node (ref "E5") (pin "14") (pinfunction "VSS_14") (pintype "power_in"))
      (node (ref "E5A") (pin "14") (pinfunction "VSS_14") (pintype "power_in"))
      (node (ref "E6") (pin "1") (pinfunction "G1_1") (pintype "input"))
      (node (ref "E6") (pin "19") (pinfunction "G2_19") (pintype "input"))
      (node (ref "E7") (pin "1") (pinfunction "G_1") (pintype "input"))
      (node (ref "E7") (pin "19") (pinfunction "G_19") (pintype "input"))
      (node (ref "J1") (pin "AC1") (pinfunction "1_AC1") (pintype "bidirectional"))
      (node (ref "J1") (pin "AC2") (pinfunction "1_AC2") (pintype "bidirectional"))
      (node (ref "J1") (pin "AF1") (pinfunction "1_AF1") (pintype "bidirectional"))
      (node (ref "J1") (pin "AF2") (pinfunction "1_AF2") (pintype "bidirectional"))
      (node (ref "J1") (pin "AN1") (pinfunction "1_AN1") (pintype "bidirectional"))
      (node (ref "J1") (pin "AN2") (pinfunction "1_AN2") (pintype "bidirectional"))
      (node (ref "J1") (pin "AT1") (pinfunction "1_AT1") (pintype "bidirectional"))
      (node (ref "J1") (pin "AT2") (pinfunction "1_AT2") (pintype "bidirectional"))
      (node (ref "J1") (pin "BC1") (pinfunction "1_BC1") (pintype "bidirectional"))
      (node (ref "J1") (pin "BC2") (pinfunction "1_BC2") (pintype "bidirectional"))
      (node (ref "J1") (pin "BF1") (pinfunction "1_BF1") (pintype "bidirectional"))
      (node (ref "J1") (pin "BF2") (pinfunction "1_BF2") (pintype "bidirectional"))
      (node (ref "J1") (pin "BN1") (pinfunction "1_BN1") (pintype "bidirectional"))
      (node (ref "J1") (pin "BN2") (pinfunction "1_BN2") (pintype "bidirectional"))
      (node (ref "J1") (pin "BT1") (pinfunction "1_BT1") (pintype "bidirectional"))
      (node (ref "J1") (pin "BT2") (pinfunction "1_BT2") (pintype "bidirectional"))
      (node (ref "J1") (pin "CC1") (pinfunction "1_CC1") (pintype "bidirectional"))
      (node (ref "J1") (pin "CC2") (pinfunction "1_CC2") (pintype "bidirectional"))
      (node (ref "J1") (pin "CF1") (pinfunction "1_CF1") (pintype "bidirectional"))
      (node (ref "J1") (pin "CF2") (pinfunction "1_CF2") (pintype "bidirectional"))
      (node (ref "J1") (pin "CN1") (pinfunction "1_CN1") (pintype "bidirectional"))
      (node (ref "J1") (pin "CN2") (pinfunction "1_CN2") (pintype "bidirectional"))
      (node (ref "J1") (pin "CT1") (pinfunction "1_CT1") (pintype "bidirectional"))
      (node (ref "J1") (pin "CT2") (pinfunction "1_CT2") (pintype "bidirectional"))
      (node (ref "J1") (pin "DC1") (pinfunction "1_DC1") (pintype "bidirectional"))
      (node (ref "J1") (pin "DC2") (pinfunction "1_DC2") (pintype "bidirectional"))
      (node (ref "J1") (pin "DF1") (pinfunction "1_DF1") (pintype "bidirectional"))
      (node (ref "J1") (pin "DF2") (pinfunction "1_DF2") (pintype "bidirectional"))
      (node (ref "J1") (pin "DN1") (pinfunction "1_DN1") (pintype "bidirectional"))
      (node (ref "J1") (pin "DN2") (pinfunction "1_DN2") (pintype "bidirectional"))
      (node (ref "J1") (pin "DT1") (pinfunction "1_DT1") (pintype "bidirectional"))
      (node (ref "J1") (pin "DT2") (pinfunction "1_DT2") (pintype "bidirectional"))
      (node (ref "J2") (pin "4") (pinfunction "4_4") (pintype "passive"))
      (node (ref "J3") (pin "6") (pinfunction "6_6") (pintype "passive"))
      (node (ref "J4") (pin "A") (pinfunction "1_A") (pintype "bidirectional"))
      (node (ref "J4") (pin "B") (pinfunction "2_B") (pintype "bidirectional"))
      (node (ref "J4") (pin "SS") (pinfunction "37_SS") (pintype "bidirectional"))
      (node (ref "J4") (pin "TT") (pinfunction "38_TT") (pintype "bidirectional"))
      (node (ref "J4") (pin "UU") (pinfunction "39_UU") (pintype "bidirectional"))
      (node (ref "J4") (pin "VV") (pinfunction "40_VV") (pintype "bidirectional"))
      (node (ref "J5") (pin "5") (pinfunction "F_5") (pintype "passive"))
      (node (ref "OSC") (pin "4") (pinfunction "GND_4") (pintype "power_in"))
      (node (ref "OSC1") (pin "7") (pinfunction "GND_7") (pintype "power_in"))
      (node (ref "R20") (pin "1") (pinfunction "1_1") (pintype "passive"))
      (node (ref "R7") (pin "1") (pinfunction "1_1") (pintype "passive"))
      (node (ref "S1") (pin "1") (pinfunction "1_1") (pintype "passive"))
      (node (ref "S1") (pin "2") (pinfunction "2_2") (pintype "passive"))
      (node (ref "S1") (pin "3") (pinfunction "3_3") (pintype "passive"))
      (node (ref "S1") (pin "4") (pinfunction "4_4") (pintype "passive"))
      (node (ref "S1") (pin "5") (pinfunction "5_5") (pintype "passive"))
      (node (ref "S1") (pin "6") (pinfunction "6_6") (pintype "passive"))
      (node (ref "S1") (pin "7") (pinfunction "7_7") (pintype "passive"))
      (node (ref "S1") (pin "8") (pinfunction "8_8") (pintype "passive"))
      (node (ref "SERIAL") (pin "1") (pinfunction "1_1") (pintype "passive"))
      (node (ref "SERIAL") (pin "2") (pinfunction "2_2") (pintype "passive"))
      (node (ref "SERIAL") (pin "3") (pinfunction "3_3") (pintype "passive"))
      (node (ref "SERIAL") (pin "4") (pinfunction "4_4") (pintype "passive"))
      (node (ref "SERIAL") (pin "5") (pinfunction "5_5") (pintype "passive"))
      (node (ref "SERIAL") (pin "6") (pinfunction "6_6") (pintype "passive"))
      (node (ref "SV2") (pin "10") (pinfunction "10_10") (pintype "passive"))
      (node (ref "SV2") (pin "2") (pinfunction "2_2") (pintype "passive"))
      (node (ref "SW2") (pin "3") (pinfunction "P_3") (pintype "passive"))
      (node (ref "SW2") (pin "4") (pinfunction "P1_4") (pintype "passive"))
      (node (ref "SW3") (pin "1") (pinfunction "1_1") (pintype "passive"))
      (node (ref "SW3") (pin "2") (pinfunction "1_2") (pintype "passive"))
      (node (ref "SW3") (pin "3") (pinfunction "1_3") (pintype "passive"))
      (node (ref "SW3") (pin "4") (pinfunction "1_4") (pintype "passive"))
      (node (ref "TS_DISABLE") (pin "3") (pinfunction "S_3") (pintype "passive"))
      (node (ref "TS_DISABLE") (pin "B") (pinfunction "B_B") (pintype "passive"))
      (node (ref "TS_DISABLE") (pin "B1") (pinfunction "B1_B1") (pintype "passive"))
      (node (ref "U1") (pin "22") (pinfunction "GND_22") (pintype "power_in"))
      (node (ref "U1") (pin "8") (pinfunction "GND_8") (pintype "power_in"))
      (node (ref "U11") (pin "1") (pinfunction "A0_1") (pintype "input"))
      (node (ref "U11") (pin "2") (pinfunction "A1_2") (pintype "input"))
      (node (ref "U11") (pin "3") (pinfunction "A2_3") (pintype "input"))
      (node (ref "U11") (pin "4") (pinfunction "GND_4") (pintype "power_in"))
      (node (ref "U11") (pin "7") (pinfunction "WP_7") (pintype "input"))
      (node (ref "U2") (pin "10") (pinfunction "VSS_10") (pintype "power_in"))
      (node (ref "U2") (pin "15") (pinfunction "A0_15") (pintype "input"))
      (node (ref "U2") (pin "16") (pinfunction "A1_16") (pintype "input"))
      (node (ref "U2") (pin "17") (pinfunction "A2_17") (pintype "input"))
      (node (ref "U7") (pin "2") (pinfunction "I1_2") (pintype "input"))
      (node (ref "U7") (pin "4") (pinfunction "I0_4") (pintype "input"))
    )
    (net (code "19") (name "INHIBIT") (class "Default")
      (node (ref "J1") (pin "AP2") (pinfunction "1_AP2") (pintype "bidirectional"))
    )
    (net (code "20") (name "INITIALIZE") (class "Default")
      (node (ref "E14") (pin "24") (pinfunction "IO16_24") (pintype "bidirectional"))
      (node (ref "J1") (pin "CR1") (pinfunction "1_CR1") (pintype "bidirectional"))
      (node (ref "Q1") (pin "1") (pinfunction "E_1") (pintype "passive"))
      (node (ref "U9") (pin "10") (pinfunction "I1_10") (pintype "input"))
      (node (ref "U9") (pin "9") (pinfunction "I0_9") (pintype "input"))
    )
    (net (code "21") (name "INT_STROBE") (class "Default")
      (node (ref "J1") (pin "BD2") (pinfunction "1_BD2") (pintype "bidirectional"))
    )
    (net (code "22") (name "MEM00") (class "Default")
      (node (ref "E2") (pin "11") (pinfunction "I/O0_11") (pintype "tri_state"))
      (node (ref "E2A") (pin "11") (pinfunction "I/O0_11") (pintype "bidirectional"))
      (node (ref "E3") (pin "3") (pinfunction "O_3") (pintype "open_collector"))
      (node (ref "E3") (pin "4") (pinfunction "I0_4") (pintype "input"))
      (node (ref "RN1") (pin "8") (pinfunction "8_8") (pintype "passive"))
    )
    (net (code "23") (name "MEM01") (class "Default")
      (node (ref "E2") (pin "12") (pinfunction "I/O1_12") (pintype "tri_state"))
      (node (ref "E2A") (pin "12") (pinfunction "I/O1_12") (pintype "bidirectional"))
      (node (ref "E3") (pin "11") (pinfunction "O_11") (pintype "open_collector"))
      (node (ref "E3") (pin "9") (pinfunction "I0_9") (pintype "input"))
      (node (ref "RN1") (pin "6") (pinfunction "6_6") (pintype "passive"))
    )
    (net (code "24") (name "MEM02") (class "Default")
      (node (ref "E2") (pin "13") (pinfunction "I/O2_13") (pintype "tri_state"))
      (node (ref "E2A") (pin "13") (pinfunction "I/O2_13") (pintype "bidirectional"))
      (node (ref "E4") (pin "3") (pinfunction "O_3") (pintype "open_collector"))
      (node (ref "E4") (pin "4") (pinfunction "I0_4") (pintype "input"))
      (node (ref "RN1") (pin "4") (pinfunction "4_4") (pintype "passive"))
    )
    (net (code "25") (name "MEM03") (class "Default")
      (node (ref "E2") (pin "15") (pinfunction "I/O3_15") (pintype "tri_state"))
      (node (ref "E2A") (pin "15") (pinfunction "I/O3_15") (pintype "bidirectional"))
      (node (ref "E4") (pin "11") (pinfunction "O_11") (pintype "open_collector"))
      (node (ref "E4") (pin "9") (pinfunction "I0_9") (pintype "input"))
      (node (ref "RN1") (pin "2") (pinfunction "2_2") (pintype "passive"))
    )
    (net (code "26") (name "MEM04") (class "Default")
      (node (ref "E10") (pin "3") (pinfunction "O_3") (pintype "open_collector"))
      (node (ref "E10") (pin "4") (pinfunction "I0_4") (pintype "input"))
      (node (ref "E5") (pin "16") (pinfunction "I/O4_16") (pintype "tri_state"))
      (node (ref "E5A") (pin "16") (pinfunction "I/O4_16") (pintype "bidirectional"))
      (node (ref "RN2") (pin "3") (pinfunction "3_3") (pintype "passive"))
    )
    (net (code "27") (name "MEM05") (class "Default")
      (node (ref "E10") (pin "11") (pinfunction "O_11") (pintype "open_collector"))
      (node (ref "E10") (pin "9") (pinfunction "I0_9") (pintype "input"))
      (node (ref "E5") (pin "17") (pinfunction "I/O5_17") (pintype "tri_state"))
      (node (ref "E5A") (pin "17") (pinfunction "I/O5_17") (pintype "bidirectional"))
      (node (ref "RN2") (pin "4") (pinfunction "4_4") (pintype "passive"))
    )
    (net (code "28") (name "MEM06") (class "Default")
      (node (ref "E11") (pin "3") (pinfunction "O_3") (pintype "open_collector"))
      (node (ref "E11") (pin "4") (pinfunction "I0_4") (pintype "input"))
      (node (ref "E5") (pin "18") (pinfunction "I/O6_18") (pintype "tri_state"))
      (node (ref "E5A") (pin "18") (pinfunction "I/O6_18") (pintype "bidirectional"))
      (node (ref "RN2") (pin "6") (pinfunction "6_6") (pintype "passive"))
    )
    (net (code "29") (name "MEM07") (class "Default")
      (node (ref "E11") (pin "11") (pinfunction "O_11") (pintype "open_collector"))
      (node (ref "E11") (pin "9") (pinfunction "I0_9") (pintype "input"))
      (node (ref "E5") (pin "19") (pinfunction "I/O7_19") (pintype "tri_state"))
      (node (ref "E5A") (pin "19") (pinfunction "I/O7_19") (pintype "bidirectional"))
      (node (ref "RN2") (pin "8") (pinfunction "8_8") (pintype "passive"))
    )
    (net (code "30") (name "MEM08") (class "Default")
      (node (ref "E12") (pin "3") (pinfunction "O_3") (pintype "open_collector"))
      (node (ref "E12") (pin "4") (pinfunction "I0_4") (pintype "input"))
      (node (ref "E5") (pin "15") (pinfunction "I/O3_15") (pintype "tri_state"))
      (node (ref "E5A") (pin "15") (pinfunction "I/O3_15") (pintype "bidirectional"))
      (node (ref "RN2") (pin "2") (pinfunction "2_2") (pintype "passive"))
    )
    (net (code "31") (name "MEM09") (class "Default")
      (node (ref "E12") (pin "11") (pinfunction "O_11") (pintype "open_collector"))
      (node (ref "E12") (pin "9") (pinfunction "I0_9") (pintype "input"))
      (node (ref "E5") (pin "13") (pinfunction "I/O2_13") (pintype "tri_state"))
      (node (ref "E5A") (pin "13") (pinfunction "I/O2_13") (pintype "bidirectional"))
      (node (ref "RN2") (pin "5") (pinfunction "5_5") (pintype "passive"))
    )
    (net (code "32") (name "MEM10") (class "Default")
      (node (ref "E13") (pin "3") (pinfunction "O_3") (pintype "open_collector"))
      (node (ref "E13") (pin "4") (pinfunction "I0_4") (pintype "input"))
      (node (ref "E5") (pin "12") (pinfunction "I/O1_12") (pintype "tri_state"))
      (node (ref "E5A") (pin "12") (pinfunction "I/O1_12") (pintype "bidirectional"))
      (node (ref "RN2") (pin "7") (pinfunction "7_7") (pintype "passive"))
    )
    (net (code "33") (name "MEM11") (class "Default")
      (node (ref "E13") (pin "11") (pinfunction "O_11") (pintype "open_collector"))
      (node (ref "E13") (pin "9") (pinfunction "I0_9") (pintype "input"))
      (node (ref "E5") (pin "11") (pinfunction "I/O0_11") (pintype "tri_state"))
      (node (ref "E5A") (pin "11") (pinfunction "I/O0_11") (pintype "bidirectional"))
      (node (ref "RN2") (pin "9") (pinfunction "9_9") (pintype "passive"))
    )
    (net (code "34") (name "MEM12") (class "Default")
      (node (ref "E2") (pin "16") (pinfunction "I/O4_16") (pintype "tri_state"))
      (node (ref "E2A") (pin "16") (pinfunction "I/O4_16") (pintype "bidirectional"))
      (node (ref "RN1") (pin "3") (pinfunction "3_3") (pintype "passive"))
    )
    (net (code "35") (name "MEM13") (class "Default")
      (node (ref "E2") (pin "17") (pinfunction "I/O5_17") (pintype "tri_state"))
      (node (ref "E2A") (pin "17") (pinfunction "I/O5_17") (pintype "bidirectional"))
      (node (ref "RN1") (pin "5") (pinfunction "5_5") (pintype "passive"))
    )
    (net (code "36") (name "MEM14") (class "Default")
      (node (ref "E2") (pin "18") (pinfunction "I/O6_18") (pintype "tri_state"))
      (node (ref "E2A") (pin "18") (pinfunction "I/O6_18") (pintype "bidirectional"))
      (node (ref "RN1") (pin "7") (pinfunction "7_7") (pintype "passive"))
    )
    (net (code "37") (name "MEM15") (class "Default")
      (node (ref "E2") (pin "19") (pinfunction "I/O7_19") (pintype "tri_state"))
      (node (ref "E2A") (pin "19") (pinfunction "I/O7_19") (pintype "bidirectional"))
      (node (ref "RN1") (pin "9") (pinfunction "9_9") (pintype "passive"))
    )
    (net (code "38") (name "Net-(B1-+-Pad+@1)") (class "Default")
      (node (ref "B1") (pin "+") (pinfunction "+_+") (pintype "passive"))
      (node (ref "B1") (pin "+@1") (pinfunction "+_+@1") (pintype "passive"))
      (node (ref "B1") (pin "+@2") (pinfunction "+_+@2") (pintype "passive"))
      (node (ref "B1") (pin "+@3") (pinfunction "+_+@3") (pintype "passive"))
      (node (ref "B1") (pin "+@4") (pinfunction "+_+@4") (pintype "passive"))
      (node (ref "D2") (pin "A") (pinfunction "A_A") (pintype "passive"))
    )
    (net (code "39") (name "Net-(E9A-D0)") (class "Default")
      (node (ref "E9") (pin "4") (pinfunction "D0_4") (pintype "input"))
      (node (ref "R23") (pin "1") (pinfunction "1_1") (pintype "passive"))
      (node (ref "S1") (pin "16") (pinfunction "16_16") (pintype "passive"))
    )
    (net (code "40") (name "Net-(E9A-D1)") (class "Default")
      (node (ref "E9") (pin "3") (pinfunction "D1_3") (pintype "input"))
      (node (ref "R23") (pin "2") (pinfunction "1_2") (pintype "passive"))
      (node (ref "S1") (pin "15") (pinfunction "15_15") (pintype "passive"))
    )
    (net (code "41") (name "Net-(E9A-D2)") (class "Default")
      (node (ref "E9") (pin "2") (pinfunction "D2_2") (pintype "input"))
      (node (ref "R23") (pin "3") (pinfunction "1_3") (pintype "passive"))
      (node (ref "S1") (pin "14") (pinfunction "14_14") (pintype "passive"))
    )
    (net (code "42") (name "Net-(E9A-D3)") (class "Default")
      (node (ref "E9") (pin "1") (pinfunction "D3_1") (pintype "input"))
      (node (ref "R23") (pin "4") (pinfunction "1_4") (pintype "passive"))
      (node (ref "S1") (pin "13") (pinfunction "13_13") (pintype "passive"))
    )
    (net (code "43") (name "Net-(E9A-D4)") (class "Default")
      (node (ref "E9") (pin "15") (pinfunction "D4_15") (pintype "input"))
      (node (ref "R23") (pin "5") (pinfunction "1_5") (pintype "passive"))
      (node (ref "S1") (pin "12") (pinfunction "12_12") (pintype "passive"))
    )
    (net (code "44") (name "Net-(E9A-D5)") (class "Default")
      (node (ref "E9") (pin "14") (pinfunction "D5_14") (pintype "input"))
      (node (ref "R23") (pin "6") (pinfunction "1_6") (pintype "passive"))
      (node (ref "S1") (pin "11") (pinfunction "11_11") (pintype "passive"))
    )
    (net (code "45") (name "Net-(E9A-D6)") (class "Default")
      (node (ref "E9") (pin "13") (pinfunction "D6_13") (pintype "input"))
      (node (ref "R23") (pin "7") (pinfunction "1_7") (pintype "passive"))
      (node (ref "S1") (pin "10") (pinfunction "10_10") (pintype "passive"))
    )
    (net (code "46") (name "Net-(E9A-D7)") (class "Default")
      (node (ref "E9") (pin "12") (pinfunction "D7_12") (pintype "input"))
      (node (ref "R23") (pin "8") (pinfunction "1_8") (pintype "passive"))
      (node (ref "S1") (pin "9") (pinfunction "9_9") (pintype "passive"))
    )
    (net (code "47") (name "Net-(Q1-B)") (class "Default")
      (node (ref "Q1") (pin "2") (pinfunction "B_2") (pintype "passive"))
      (node (ref "R10") (pin "2") (pinfunction "2_2") (pintype "passive"))
    )
    (net (code "48") (name "Net-(Q1-C)") (class "Default")
      (node (ref "Q1") (pin "3") (pinfunction "C_3") (pintype "passive"))
      (node (ref "R5") (pin "1") (pinfunction "1_1") (pintype "passive"))
    )
    (net (code "49") (name "Net-(Q2-B)") (class "Default")
      (node (ref "Q2") (pin "2") (pinfunction "B_2") (pintype "passive"))
      (node (ref "R11") (pin "2") (pinfunction "2_2") (pintype "passive"))
    )
    (net (code "50") (name "Net-(Q2-C)") (class "Default")
      (node (ref "Q2") (pin "3") (pinfunction "C_3") (pintype "passive"))
      (node (ref "R6") (pin "1") (pinfunction "1_1") (pintype "passive"))
    )
    (net (code "51") (name "Net-(Q3-B)") (class "Default")
      (node (ref "Q3") (pin "2") (pinfunction "B_2") (pintype "passive"))
      (node (ref "R24") (pin "2") (pinfunction "2_2") (pintype "passive"))
    )
    (net (code "52") (name "Net-(SW2-S)") (class "Default")
      (node (ref "R12") (pin "2") (pinfunction "2_2") (pintype "passive"))
      (node (ref "SW2") (pin "1") (pinfunction "S_1") (pintype "passive"))
      (node (ref "SW2") (pin "2") (pinfunction "S1_2") (pintype "passive"))
    )
    (net (code "53") (name "Net-(SW3A-2)") (class "Default")
      (node (ref "R9") (pin "2") (pinfunction "2_2") (pintype "passive"))
      (node (ref "SW3") (pin "8") (pinfunction "2_8") (pintype "passive"))
    )
    (net (code "54") (name "Net-(SW3B-2)") (class "Default")
      (node (ref "R8") (pin "2") (pinfunction "2_2") (pintype "passive"))
      (node (ref "SW3") (pin "7") (pinfunction "2_7") (pintype "passive"))
    )
    (net (code "55") (name "Net-(SW3C-2)") (class "Default")
      (node (ref "R4") (pin "2") (pinfunction "2_2") (pintype "passive"))
      (node (ref "SW3") (pin "6") (pinfunction "2_6") (pintype "passive"))
    )
    (net (code "56") (name "Net-(SW3D-2)") (class "Default")
      (node (ref "R3") (pin "2") (pinfunction "2_2") (pintype "passive"))
      (node (ref "SW3") (pin "5") (pinfunction "2_5") (pintype "passive"))
    )
    (net (code "57") (name "Net-(U1-PB6(XTAL1{slash}TOSC1))") (class "Default")
      (node (ref "C9") (pin "1") (pinfunction "1_1") (pintype "passive"))
      (node (ref "R18") (pin "1") (pinfunction "1_1") (pintype "passive"))
      (node (ref "U1") (pin "9") (pinfunction "PB6(XTAL1/TOSC1)_9") (pintype "bidirectional"))
      (node (ref "Y1") (pin "2") (pinfunction "2_2") (pintype "passive"))
    )
    (net (code "58") (name "Net-(U1-PB7(XTAL2{slash}TOSC2))") (class "Default")
      (node (ref "C7") (pin "1") (pinfunction "1_1") (pintype "passive"))
      (node (ref "R18") (pin "2") (pinfunction "2_2") (pintype "passive"))
      (node (ref "U1") (pin "10") (pinfunction "PB7(XTAL2/TOSC2)_10") (pintype "bidirectional"))
      (node (ref "Y1") (pin "1") (pinfunction "1_1") (pintype "passive"))
    )
    (net (code "59") (name "Net-(U1-PD0(RXD))") (class "Default")
      (node (ref "R16") (pin "1") (pinfunction "1_1") (pintype "passive"))
      (node (ref "U1") (pin "2") (pinfunction "PD0(RXD)_2") (pintype "bidirectional"))
    )
    (net (code "60") (name "Net-(U1-PD1(TXD))") (class "Default")
      (node (ref "R17") (pin "1") (pinfunction "1_1") (pintype "passive"))
      (node (ref "U1") (pin "3") (pinfunction "PD1(TXD)_3") (pintype "bidirectional"))
    )
    (net (code "61") (name "Net-(U8A-O)") (class "Default")
      (node (ref "U8") (pin "12") (pinfunction "O_12") (pintype "output"))
      (node (ref "U8") (pin "3") (pinfunction "I0_3") (pintype "input"))
      (node (ref "U8") (pin "4") (pinfunction "I1_4") (pintype "input"))
      (node (ref "U8") (pin "5") (pinfunction "I2_5") (pintype "input"))
    )
    (net (code "62") (name "Net-(U8C-I0)") (class "Default")
      (node (ref "U8") (pin "9") (pinfunction "I0_9") (pintype "input"))
      (node (ref "U9") (pin "8") (pinfunction "O_8") (pintype "output"))
    )
    (net (code "63") (name "Net-(U8C-I1)") (class "Default")
      (node (ref "U8") (pin "10") (pinfunction "I1_10") (pintype "input"))
      (node (ref "U9") (pin "6") (pinfunction "O_6") (pintype "output"))
    )
    (net (code "64") (name "Net-(U8C-O)") (class "Default")
      (node (ref "U8") (pin "8") (pinfunction "O_8") (pintype "output"))
      (node (ref "U9") (pin "13") (pinfunction "I1_13") (pintype "input"))
      (node (ref "U9") (pin "2") (pinfunction "I1_2") (pintype "input"))
    )
    (net (code "65") (name "Net-(U9A-O)") (class "Default")
      (node (ref "U9") (pin "12") (pinfunction "I0_12") (pintype "input"))
      (node (ref "U9") (pin "3") (pinfunction "O_3") (pintype "output"))
    )
    (net (code "66") (name "Net-(U10A-C1+)") (class "Default")
      (node (ref "C14") (pin "1") (pinfunction "1_1") (pintype "passive"))
      (node (ref "U10") (pin "1") (pinfunction "C1+_1") (pintype "bidirectional"))
    )
    (net (code "67") (name "Net-(U10A-C1-)") (class "Default")
      (node (ref "C14") (pin "2") (pinfunction "2_2") (pintype "passive"))
      (node (ref "U10") (pin "3") (pinfunction "C1-_3") (pintype "bidirectional"))
    )
    (net (code "68") (name "Net-(U10A-C2+)") (class "Default")
      (node (ref "C15") (pin "1") (pinfunction "1_1") (pintype "passive"))
      (node (ref "U10") (pin "4") (pinfunction "C2+_4") (pintype "bidirectional"))
    )
    (net (code "69") (name "Net-(U10A-C2-)") (class "Default")
      (node (ref "C15") (pin "2") (pinfunction "2_2") (pintype "passive"))
      (node (ref "U10") (pin "5") (pinfunction "C2-_5") (pintype "bidirectional"))
    )
    (net (code "70") (name "Net-(U10A-V+)") (class "Default")
      (node (ref "C16") (pin "1") (pinfunction "1_1") (pintype "passive"))
      (node (ref "U10") (pin "2") (pinfunction "V+_2") (pintype "bidirectional"))
    )
    (net (code "71") (name "Net-(U10A-V-)") (class "Default")
      (node (ref "C17") (pin "2") (pinfunction "2_2") (pintype "passive"))
      (node (ref "U10") (pin "6") (pinfunction "V-_6") (pintype "bidirectional"))
    )
    (net (code "72") (name "OE") (class "Default")
      (node (ref "E10") (pin "10") (pinfunction "I1_10") (pintype "input"))
      (node (ref "E10") (pin "5") (pinfunction "I1_5") (pintype "input"))
      (node (ref "E11") (pin "10") (pinfunction "I1_10") (pintype "input"))
      (node (ref "E11") (pin "5") (pinfunction "I1_5") (pintype "input"))
      (node (ref "E12") (pin "10") (pinfunction "I1_10") (pintype "input"))
      (node (ref "E12") (pin "5") (pinfunction "I1_5") (pintype "input"))
      (node (ref "E13") (pin "10") (pinfunction "I1_10") (pintype "input"))
      (node (ref "E13") (pin "5") (pinfunction "I1_5") (pintype "input"))
      (node (ref "E3") (pin "10") (pinfunction "I1_10") (pintype "input"))
      (node (ref "E3") (pin "5") (pinfunction "I1_5") (pintype "input"))
      (node (ref "E4") (pin "10") (pinfunction "I1_10") (pintype "input"))
      (node (ref "E4") (pin "5") (pinfunction "I1_5") (pintype "input"))
      (node (ref "E6") (pin "12") (pinfunction "Y7_12") (pintype "tri_state"))
    )
    (net (code "73") (name "POWER_OK") (class "Default")
      (node (ref "E14") (pin "39") (pinfunction "IO28_39") (pintype "bidirectional"))
      (node (ref "J1") (pin "BV2") (pinfunction "1_BV2") (pintype "bidirectional"))
      (node (ref "R24") (pin "1") (pinfunction "1_1") (pintype "passive"))
    )
    (net (code "74") (name "PROG") (class "Default")
      (node (ref "C11") (pin "2") (pinfunction "2_2") (pintype "passive"))
      (node (ref "J2") (pin "1") (pinfunction "1_1") (pintype "passive"))
      (node (ref "R20") (pin "2") (pinfunction "2_2") (pintype "passive"))
      (node (ref "SV1") (pin "1") (pinfunction "1_1") (pintype "passive"))
    )
    (net (code "75") (name "PULSE_LA") (class "Default")
      (node (ref "E14") (pin "2") (pinfunction "IN/GCLK2/OE2_2") (pintype "input"))
      (node (ref "J1") (pin "DR2") (pinfunction "1_DR2") (pintype "bidirectional"))
      (node (ref "Q2") (pin "1") (pinfunction "E_1") (pintype "passive"))
    )
    (net (code "76") (name "RETURN") (class "Default")
      (node (ref "J1") (pin "AR2") (pinfunction "1_AR2") (pintype "bidirectional"))
    )
    (net (code "77") (name "ROM_ADDR") (class "Default")
      (node (ref "E6") (pin "11") (pinfunction "Y8_11") (pintype "tri_state"))
      (node (ref "E9") (pin "7") (pinfunction "G_7") (pintype "input"))
    )
    (net (code "78") (name "RXD") (class "Default")
      (node (ref "J2") (pin "2") (pinfunction "2_2") (pintype "passive"))
      (node (ref "R16") (pin "2") (pinfunction "2_2") (pintype "passive"))
      (node (ref "SV1") (pin "3") (pinfunction "3_3") (pintype "passive"))
    )
    (net (code "79") (name "RXD232") (class "Default")
      (node (ref "J4") (pin "J") (pinfunction "8_J") (pintype "bidirectional"))
      (node (ref "J5") (pin "2") (pinfunction "F_2") (pintype "passive"))
      (node (ref "U10") (pin "8") (pinfunction "R2IN_8") (pintype "input"))
    )
    (net (code "80") (name "RXDTTL") (class "Default")
      (node (ref "E14") (pin "75") (pinfunction "IO55_75") (pintype "bidirectional"))
      (node (ref "SV1") (pin "4") (pinfunction "4_4") (pintype "passive"))
      (node (ref "U10") (pin "9") (pinfunction "R2OUT_9") (pintype "output"))
    )
    (net (code "81") (name "R_RUN") (class "Default")
      (node (ref "R2") (pin "1") (pinfunction "1_1") (pintype "passive"))
      (node (ref "U1") (pin "14") (pinfunction "PB0(ICP)_14") (pintype "bidirectional"))
    )
    (net (code "82") (name "R_SW") (class "Default")
      (node (ref "C10") (pin "1") (pinfunction "1_1") (pintype "passive"))
      (node (ref "R1") (pin "1") (pinfunction "1_1") (pintype "passive"))
      (node (ref "R12") (pin "1") (pinfunction "1_1") (pintype "passive"))
      (node (ref "U1") (pin "15") (pinfunction "PB1(OC1A)_15") (pintype "bidirectional"))
    )
    (net (code "83") (name "SCL") (class "Default")
      (node (ref "R22") (pin "1") (pinfunction "1_1") (pintype "passive"))
      (node (ref "U1") (pin "28") (pinfunction "PC5(ADC5/SCL)_28") (pintype "bidirectional"))
      (node (ref "U11") (pin "6") (pinfunction "SCL_6") (pintype "input"))
      (node (ref "U2") (pin "12") (pinfunction "SCL_12") (pintype "input"))
    )
    (net (code "84") (name "SDA") (class "Default")
      (node (ref "R21") (pin "1") (pinfunction "1_1") (pintype "passive"))
      (node (ref "U1") (pin "27") (pinfunction "PC4(ADC4/SDA)_27") (pintype "bidirectional"))
      (node (ref "U11") (pin "5") (pinfunction "SDA_5") (pintype "bidirectional"))
      (node (ref "U2") (pin "13") (pinfunction "SDA_13") (pintype "bidirectional"))
    )
    (net (code "85") (name "SET_FF") (class "Default")
      (node (ref "U1") (pin "4") (pinfunction "PD2(INT0)_4") (pintype "bidirectional"))
      (node (ref "U9") (pin "1") (pinfunction "I0_1") (pintype "input"))
    )
    (net (code "86") (name "SHOW_DATA") (class "Default")
      (node (ref "U1") (pin "5") (pinfunction "PD3(INT1)_5") (pintype "bidirectional"))
      (node (ref "U8") (pin "1") (pinfunction "I0_1") (pintype "input"))
    )
    (net (code "87") (name "SOURCE") (class "Default")
      (node (ref "E6") (pin "3") (pinfunction "A2_3") (pintype "input"))
      (node (ref "J1") (pin "AL2") (pinfunction "1_AL2") (pintype "bidirectional"))
    )
    (net (code "88") (name "STROBE") (class "Default")
      (node (ref "J1") (pin "AM2") (pinfunction "1_AM2") (pintype "bidirectional"))
    )
    (net (code "89") (name "SW") (class "Default")
      (node (ref "J1") (pin "DV2") (pinfunction "1_DV2") (pintype "bidirectional"))
      (node (ref "R1") (pin "2") (pinfunction "2_2") (pintype "passive"))
    )
    (net (code "90") (name "TCK2") (class "Default")
      (node (ref "E14") (pin "62") (pinfunction "TCK_62") (pintype "bidirectional"))
      (node (ref "SV2") (pin "1") (pinfunction "1_1") (pintype "passive"))
    )
    (net (code "91") (name "TDI2") (class "Default")
      (node (ref "E14") (pin "14") (pinfunction "TDI_14") (pintype "bidirectional"))
      (node (ref "SV2") (pin "9") (pinfunction "9_9") (pintype "passive"))
    )
    (net (code "92") (name "TDO2") (class "Default")
      (node (ref "E14") (pin "71") (pinfunction "TDO_71") (pintype "bidirectional"))
      (node (ref "SV2") (pin "3") (pinfunction "3_3") (pintype "passive"))
    )
    (net (code "93") (name "TMS2") (class "Default")
      (node (ref "E14") (pin "23") (pinfunction "TMS_23") (pintype "bidirectional"))
      (node (ref "SV2") (pin "5") (pinfunction "5_5") (pintype "passive"))
    )
    (net (code "94") (name "TP1") (class "Default")
      (node (ref "J1") (pin "CD2") (pinfunction "1_CD2") (pintype "bidirectional"))
    )
    (net (code "95") (name "TP2") (class "Default")
      (node (ref "E14") (pin "34") (pinfunction "IO24_34") (pintype "bidirectional"))
      (node (ref "J1") (pin "CE2") (pinfunction "1_CE2") (pintype "bidirectional"))
    )
    (net (code "96") (name "TP3") (class "Default")
      (node (ref "E14") (pin "31") (pinfunction "IO22_31") (pintype "bidirectional"))
      (node (ref "J1") (pin "CH2") (pinfunction "1_CH2") (pintype "bidirectional"))
    )
    (net (code "97") (name "TP4") (class "Default")
      (node (ref "E14") (pin "30") (pinfunction "IO21_30") (pintype "bidirectional"))
      (node (ref "E6") (pin "2") (pinfunction "A1_2") (pintype "input"))
      (node (ref "J1") (pin "CJ2") (pinfunction "1_CJ2") (pintype "bidirectional"))
      (node (ref "U9") (pin "4") (pinfunction "I0_4") (pintype "input"))
      (node (ref "U9") (pin "5") (pinfunction "I1_5") (pintype "input"))
    )
    (net (code "98") (name "TP_AA1") (class "Default")
      (node (ref "E14") (pin "74") (pinfunction "IO54_74") (pintype "bidirectional"))
      (node (ref "J1") (pin "AA1") (pinfunction "1_AA1") (pintype "bidirectional"))
      (node (ref "RN3") (pin "4") (pinfunction "4_4") (pintype "passive"))
      (node (ref "SERIAL") (pin "10") (pinfunction "10_10") (pintype "passive"))
    )
    (net (code "99") (name "TP_AB1") (class "Default")
      (node (ref "E14") (pin "73") (pinfunction "IO53_73") (pintype "bidirectional"))
      (node (ref "J1") (pin "AB1") (pinfunction "1_AB1") (pintype "bidirectional"))
      (node (ref "RN3") (pin "5") (pinfunction "5_5") (pintype "passive"))
      (node (ref "SERIAL") (pin "9") (pinfunction "9_9") (pintype "passive"))
    )
    (net (code "100") (name "TP_BA1") (class "Default")
      (node (ref "E14") (pin "56") (pinfunction "IO41_56") (pintype "bidirectional"))
      (node (ref "J1") (pin "BA1") (pinfunction "1_BA1") (pintype "bidirectional"))
      (node (ref "RN3") (pin "6") (pinfunction "6_6") (pintype "passive"))
      (node (ref "SERIAL") (pin "8") (pinfunction "8_8") (pintype "passive"))
    )
    (net (code "101") (name "TP_BB1") (class "Default")
      (node (ref "E14") (pin "55") (pinfunction "IO40_55") (pintype "bidirectional"))
      (node (ref "J1") (pin "BB1") (pinfunction "1_BB1") (pintype "bidirectional"))
      (node (ref "RN3") (pin "7") (pinfunction "7_7") (pintype "passive"))
      (node (ref "SERIAL") (pin "7") (pinfunction "7_7") (pintype "passive"))
    )
    (net (code "102") (name "TXD") (class "Default")
      (node (ref "J2") (pin "3") (pinfunction "3_3") (pintype "passive"))
      (node (ref "R17") (pin "2") (pinfunction "2_2") (pintype "passive"))
      (node (ref "SV1") (pin "5") (pinfunction "5_5") (pintype "passive"))
    )
    (net (code "103") (name "TXD232") (class "Default")
      (node (ref "J4") (pin "F") (pinfunction "6_F") (pintype "bidirectional"))
      (node (ref "J5") (pin "3") (pinfunction "F_3") (pintype "passive"))
      (node (ref "U10") (pin "7") (pinfunction "T2OUT_7") (pintype "output"))
    )
    (net (code "104") (name "TXDTTL") (class "Default")
      (node (ref "E14") (pin "76") (pinfunction "IO56_76") (pintype "bidirectional"))
      (node (ref "SV1") (pin "6") (pinfunction "6_6") (pintype "passive"))
      (node (ref "U10") (pin "10") (pinfunction "T2IN_10") (pintype "input"))
    )
    (net (code "105") (name "V+") (class "Default")
      (node (ref "C20") (pin "1") (pinfunction "1_1") (pintype "passive"))
      (node (ref "C21") (pin "1") (pinfunction "1_1") (pintype "passive"))
      (node (ref "D2") (pin "C") (pinfunction "C_C") (pintype "passive"))
      (node (ref "D3") (pin "C") (pinfunction "C_C") (pintype "passive"))
      (node (ref "E2") (pin "28") (pinfunction "VCC_28") (pintype "power_in"))
      (node (ref "E2A") (pin "28") (pinfunction "VCC_28") (pintype "power_in"))
      (node (ref "E5") (pin "28") (pinfunction "VCC_28") (pintype "power_in"))
      (node (ref "E5A") (pin "28") (pinfunction "VCC_28") (pintype "power_in"))
      (node (ref "R15") (pin "2") (pinfunction "2_2") (pintype "passive"))
    )
    (net (code "106") (name "VCC") (class "Default")
      (node (ref "C1") (pin "1") (pinfunction "1_1") (pintype "passive"))
      (node (ref "C12") (pin "1") (pinfunction "1_1") (pintype "passive"))
      (node (ref "C13") (pin "1") (pinfunction "1_1") (pintype "passive"))
      (node (ref "C16") (pin "2") (pinfunction "2_2") (pintype "passive"))
      (node (ref "C18") (pin "1") (pinfunction "1_1") (pintype "passive"))
      (node (ref "C19") (pin "1") (pinfunction "1_1") (pintype "passive"))
      (node (ref "C2") (pin "1") (pinfunction "1_1") (pintype "passive"))
      (node (ref "C23") (pin "1") (pinfunction "1_1") (pintype "passive"))
      (node (ref "C24") (pin "1") (pinfunction "1_1") (pintype "passive"))
      (node (ref "C25") (pin "1") (pinfunction "1_1") (pintype "passive"))
      (node (ref "C26") (pin "1") (pinfunction "1_1") (pintype "passive"))
      (node (ref "C27") (pin "1") (pinfunction "1_1") (pintype "passive"))
      (node (ref "C28") (pin "1") (pinfunction "1_1") (pintype "passive"))
      (node (ref "C29") (pin "1") (pinfunction "1_1") (pintype "passive"))
      (node (ref "C3") (pin "1") (pinfunction "1_1") (pintype "passive"))
      (node (ref "C30") (pin "+") (pinfunction "+_+") (pintype "passive"))
      (node (ref "C31") (pin "1") (pinfunction "1_1") (pintype "passive"))
      (node (ref "C32") (pin "1") (pinfunction "1_1") (pintype "passive"))
      (node (ref "C33") (pin "1") (pinfunction "1_1") (pintype "passive"))
      (node (ref "C34") (pin "+") (pinfunction "+_+") (pintype "passive"))
      (node (ref "C35") (pin "+") (pinfunction "+_+") (pintype "passive"))
      (node (ref "C36") (pin "1") (pinfunction "1_1") (pintype "passive"))
      (node (ref "C37") (pin "1") (pinfunction "1_1") (pintype "passive"))
      (node (ref "C4") (pin "1") (pinfunction "1_1") (pintype "passive"))
      (node (ref "C45") (pin "1") (pinfunction "1_1") (pintype "passive"))
      (node (ref "C5") (pin "1") (pinfunction "1_1") (pintype "passive"))
      (node (ref "C6") (pin "1") (pinfunction "1_1") (pintype "passive"))
      (node (ref "C8") (pin "1") (pinfunction "1_1") (pintype "passive"))
      (node (ref "D1") (pin "C") (pinfunction "C_C") (pintype "passive"))
      (node (ref "D3") (pin "A") (pinfunction "A_A") (pintype "passive"))
      (node (ref "J1") (pin "AA2") (pinfunction "1_AA2") (pintype "bidirectional"))
      (node (ref "J1") (pin "BA2") (pinfunction "1_BA2") (pintype "bidirectional"))
      (node (ref "J1") (pin "CA2") (pinfunction "1_CA2") (pintype "bidirectional"))
      (node (ref "J3") (pin "2") (pinfunction "2_2") (pintype "passive"))
      (node (ref "OSC") (pin "8") (pinfunction "VCC_8") (pintype "power_in"))
      (node (ref "OSC1") (pin "14") (pinfunction "VCC_14") (pintype "power_in"))
      (node (ref "R13") (pin "2") (pinfunction "2_2") (pintype "passive"))
      (node (ref "R14") (pin "2") (pinfunction "2_2") (pintype "passive"))
      (node (ref "R19") (pin "2") (pinfunction "2_2") (pintype "passive"))
      (node (ref "R21") (pin "2") (pinfunction "2_2") (pintype "passive"))
      (node (ref "R22") (pin "2") (pinfunction "2_2") (pintype "passive"))
      (node (ref "R23") (pin "10") (pinfunction "2_10") (pintype "passive"))
      (node (ref "R23") (pin "11") (pinfunction "2_11") (pintype "passive"))
      (node (ref "R23") (pin "12") (pinfunction "2_12") (pintype "passive"))
      (node (ref "R23") (pin "13") (pinfunction "2_13") (pintype "passive"))
      (node (ref "R23") (pin "14") (pinfunction "2_14") (pintype "passive"))
      (node (ref "R23") (pin "15") (pinfunction "2_15") (pintype "passive"))
      (node (ref "R23") (pin "16") (pinfunction "2_16") (pintype "passive"))
      (node (ref "R23") (pin "9") (pinfunction "2_9") (pintype "passive"))
      (node (ref "R5") (pin "2") (pinfunction "2_2") (pintype "passive"))
      (node (ref "R6") (pin "2") (pinfunction "2_2") (pintype "passive"))
      (node (ref "RN1") (pin "1") (pinfunction "1_1") (pintype "passive"))
      (node (ref "RN2") (pin "1") (pinfunction "1_1") (pintype "passive"))
      (node (ref "RN3") (pin "1") (pinfunction "1_1") (pintype "passive"))
      (node (ref "SV2") (pin "4") (pinfunction "4_4") (pintype "passive"))
      (node (ref "U1") (pin "20") (pinfunction "AVCC_20") (pintype "power_in"))
      (node (ref "U1") (pin "21") (pinfunction "AREF_21") (pintype "passive"))
      (node (ref "U1") (pin "7") (pinfunction "VCC_7") (pintype "power_in"))
      (node (ref "U11") (pin "8") (pinfunction "VCC_8") (pintype "power_in"))
      (node (ref "U2") (pin "18") (pinfunction "~{RESET}_18") (pintype "input"))
      (node (ref "U2") (pin "9") (pinfunction "VDD_9") (pintype "power_in"))
      (node (ref "U7") (pin "12") (pinfunction "I0_12") (pintype "input"))
      (node (ref "U7") (pin "13") (pinfunction "I1_13") (pintype "input"))
      (node (ref "VCCINT") (pin "1") (pinfunction "1_1") (pintype "bidirectional"))
      (node (ref "VCCIO") (pin "1") (pinfunction "1_1") (pintype "bidirectional"))
    )
    (net (code "107") (name "VCCINT") (class "Default")
      (node (ref "C41") (pin "1") (pinfunction "1_1") (pintype "passive"))
      (node (ref "C43") (pin "1") (pinfunction "1_1") (pintype "passive"))
      (node (ref "VCCINT") (pin "2") (pinfunction "2_2") (pintype "bidirectional"))
    )
    (net (code "108") (name "VCCIO") (class "Default")
      (node (ref "C42") (pin "1") (pinfunction "1_1") (pintype "passive"))
      (node (ref "C44") (pin "1") (pinfunction "1_1") (pintype "passive"))
      (node (ref "VCCIO") (pin "2") (pinfunction "2_2") (pintype "bidirectional"))
    )
    (net (code "109") (name "WE") (class "Default")
      (node (ref "E10") (pin "13") (pinfunction "I1_13") (pintype "input"))
      (node (ref "E10") (pin "2") (pinfunction "I1_2") (pintype "input"))
      (node (ref "E11") (pin "13") (pinfunction "I1_13") (pintype "input"))
      (node (ref "E11") (pin "2") (pinfunction "I1_2") (pintype "input"))
      (node (ref "E12") (pin "13") (pinfunction "I1_13") (pintype "input"))
      (node (ref "E12") (pin "2") (pinfunction "I1_2") (pintype "input"))
      (node (ref "E13") (pin "13") (pinfunction "I1_13") (pintype "input"))
      (node (ref "E13") (pin "2") (pinfunction "I1_2") (pintype "input"))
      (node (ref "E3") (pin "13") (pinfunction "I1_13") (pintype "input"))
      (node (ref "E3") (pin "2") (pinfunction "I1_2") (pintype "input"))
      (node (ref "E4") (pin "13") (pinfunction "I1_13") (pintype "input"))
      (node (ref "E4") (pin "2") (pinfunction "I1_2") (pintype "input"))
      (node (ref "E6") (pin "13") (pinfunction "Y6_13") (pintype "tri_state"))
    )
    (net (code "110") (name "WRITE") (class "Default")
      (node (ref "E8") (pin "3") (pinfunction "I0_3") (pintype "input"))
      (node (ref "J1") (pin "AS2") (pinfunction "1_AS2") (pintype "bidirectional"))
    )
    (net (code "111") (name "W_DATA_00") (class "Default")
      (node (ref "U2") (pin "7") (pinfunction "GPB6_7") (pintype "bidirectional"))
      (node (ref "U3") (pin "2") (pinfunction "I1_2") (pintype "input"))
    )
    (net (code "112") (name "W_DATA_01") (class "Default")
      (node (ref "U2") (pin "6") (pinfunction "GPB5_6") (pintype "bidirectional"))
      (node (ref "U3") (pin "4") (pinfunction "I0_4") (pintype "input"))
    )
    (net (code "113") (name "W_DATA_02") (class "Default")
      (node (ref "U2") (pin "5") (pinfunction "GPB4_5") (pintype "bidirectional"))
      (node (ref "U3") (pin "12") (pinfunction "I0_12") (pintype "input"))
    )
    (net (code "114") (name "W_DATA_03") (class "Default")
      (node (ref "U2") (pin "3") (pinfunction "GPB2_3") (pintype "bidirectional"))
      (node (ref "U3") (pin "9") (pinfunction "I0_9") (pintype "input"))
    )
    (net (code "115") (name "W_DATA_04") (class "Default")
      (node (ref "U2") (pin "2") (pinfunction "GPB1_2") (pintype "bidirectional"))
      (node (ref "U4") (pin "2") (pinfunction "I1_2") (pintype "input"))
    )
    (net (code "116") (name "W_DATA_05") (class "Default")
      (node (ref "U2") (pin "1") (pinfunction "GPB0_1") (pintype "bidirectional"))
      (node (ref "U4") (pin "4") (pinfunction "I0_4") (pintype "input"))
    )
    (net (code "117") (name "W_DATA_06") (class "Default")
      (node (ref "U2") (pin "27") (pinfunction "GPA6_27") (pintype "bidirectional"))
      (node (ref "U4") (pin "12") (pinfunction "I0_12") (pintype "input"))
    )
    (net (code "118") (name "W_DATA_07") (class "Default")
      (node (ref "U2") (pin "26") (pinfunction "GPA5_26") (pintype "bidirectional"))
      (node (ref "U4") (pin "9") (pinfunction "I0_9") (pintype "input"))
    )
    (net (code "119") (name "W_DATA_08") (class "Default")
      (node (ref "U2") (pin "25") (pinfunction "GPA4_25") (pintype "bidirectional"))
      (node (ref "U5") (pin "2") (pinfunction "I1_2") (pintype "input"))
    )
    (net (code "120") (name "W_DATA_09") (class "Default")
      (node (ref "U2") (pin "23") (pinfunction "GPA2_23") (pintype "bidirectional"))
      (node (ref "U5") (pin "4") (pinfunction "I0_4") (pintype "input"))
    )
    (net (code "121") (name "W_DATA_10") (class "Default")
      (node (ref "U2") (pin "22") (pinfunction "GPA1_22") (pintype "bidirectional"))
      (node (ref "U5") (pin "12") (pinfunction "I0_12") (pintype "input"))
    )
    (net (code "122") (name "W_DATA_11") (class "Default")
      (node (ref "U2") (pin "21") (pinfunction "GPA0_21") (pintype "bidirectional"))
      (node (ref "U5") (pin "9") (pinfunction "I0_9") (pintype "input"))
    )
    (net (code "123") (name "W_INITIALIZE") (class "Default")
      (node (ref "R10") (pin "1") (pinfunction "1_1") (pintype "passive"))
      (node (ref "R13") (pin "1") (pinfunction "1_1") (pintype "passive"))
      (node (ref "U1") (pin "23") (pinfunction "PC0(ADC0)_23") (pintype "bidirectional"))
    )
    (net (code "124") (name "W_PULSE_LA") (class "Default")
      (node (ref "R11") (pin "1") (pinfunction "1_1") (pintype "passive"))
      (node (ref "R14") (pin "1") (pinfunction "1_1") (pintype "passive"))
      (node (ref "U1") (pin "24") (pinfunction "PC1(ADC1)_24") (pintype "bidirectional"))
    )
    (net (code "125") (name "W_STOP") (class "Default")
      (node (ref "U1") (pin "26") (pinfunction "PC3(ADC3)_26") (pintype "bidirectional"))
      (node (ref "U7") (pin "10") (pinfunction "I1_10") (pintype "input"))
      (node (ref "U7") (pin "9") (pinfunction "I0_9") (pintype "input"))
    )
    (net (code "126") (name "unconnected-(E1A-Y4-Pad12)") (class "Default")
      (node (ref "E1") (pin "12") (pinfunction "Y4_12") (pintype "tri_state"))
    )
    (net (code "127") (name "unconnected-(E9A-W-Pad6)") (class "Default")
      (node (ref "E9") (pin "6") (pinfunction "W_6") (pintype "output"))
    )
    (net (code "128") (name "unconnected-(J1BN-1-PadBS2)") (class "Default")
      (node (ref "J1") (pin "BS2") (pinfunction "1_BS2") (pintype "bidirectional"))
    )
    (net (code "129") (name "unconnected-(J1BW-1-PadCB1)") (class "Default")
      (node (ref "J1") (pin "CB1") (pinfunction "1_CB1") (pintype "bidirectional"))
    )
    (net (code "130") (name "unconnected-(J1DE-1-PadDA1)") (class "Default")
      (node (ref "J1") (pin "DA1") (pinfunction "1_DA1") (pintype "bidirectional"))
    )
    (net (code "131") (name "unconnected-(J1DG-1-PadDB1)") (class "Default")
      (node (ref "J1") (pin "DB1") (pinfunction "1_DB1") (pintype "bidirectional"))
    )
    (net (code "132") (name "unconnected-(J4-3-PadC)") (class "Default")
      (node (ref "J4") (pin "C") (pinfunction "3_C") (pintype "bidirectional"))
    )
    (net (code "133") (name "unconnected-(J4-4-PadD)") (class "Default")
      (node (ref "J4") (pin "D") (pinfunction "4_D") (pintype "bidirectional"))
    )
    (net (code "134") (name "unconnected-(J4-5-PadE)") (class "Default")
      (node (ref "J4") (pin "E") (pinfunction "5_E") (pintype "bidirectional"))
    )
    (net (code "135") (name "unconnected-(J4-7-PadH)") (class "Default")
      (node (ref "J4") (pin "H") (pinfunction "7_H") (pintype "bidirectional"))
    )
    (net (code "136") (name "unconnected-(J4-9-PadK)") (class "Default")
      (node (ref "J4") (pin "K") (pinfunction "9_K") (pintype "bidirectional"))
    )
    (net (code "137") (name "unconnected-(J4-10-PadL)") (class "Default")
      (node (ref "J4") (pin "L") (pinfunction "10_L") (pintype "bidirectional"))
    )
    (net (code "138") (name "unconnected-(J4-11-PadM)") (class "Default")
      (node (ref "J4") (pin "M") (pinfunction "11_M") (pintype "bidirectional"))
    )
    (net (code "139") (name "unconnected-(J4-12-PadN)") (class "Default")
      (node (ref "J4") (pin "N") (pinfunction "12_N") (pintype "bidirectional"))
    )
    (net (code "140") (name "unconnected-(J4-13-PadP)") (class "Default")
      (node (ref "J4") (pin "P") (pinfunction "13_P") (pintype "bidirectional"))
    )
    (net (code "141") (name "unconnected-(J4-14-PadR)") (class "Default")
      (node (ref "J4") (pin "R") (pinfunction "14_R") (pintype "bidirectional"))
    )
    (net (code "142") (name "unconnected-(J4-15-PadS)") (class "Default")
      (node (ref "J4") (pin "S") (pinfunction "15_S") (pintype "bidirectional"))
    )
    (net (code "143") (name "unconnected-(J4-16-PadT)") (class "Default")
      (node (ref "J4") (pin "T") (pinfunction "16_T") (pintype "bidirectional"))
    )
    (net (code "144") (name "unconnected-(J4-17-PadU)") (class "Default")
      (node (ref "J4") (pin "U") (pinfunction "17_U") (pintype "bidirectional"))
    )
    (net (code "145") (name "unconnected-(J4-18-PadV)") (class "Default")
      (node (ref "J4") (pin "V") (pinfunction "18_V") (pintype "bidirectional"))
    )
    (net (code "146") (name "unconnected-(J4-19-PadW)") (class "Default")
      (node (ref "J4") (pin "W") (pinfunction "19_W") (pintype "bidirectional"))
    )
    (net (code "147") (name "unconnected-(J4-20-PadX)") (class "Default")
      (node (ref "J4") (pin "X") (pinfunction "20_X") (pintype "bidirectional"))
    )
    (net (code "148") (name "unconnected-(J4-21-PadY)") (class "Default")
      (node (ref "J4") (pin "Y") (pinfunction "21_Y") (pintype "bidirectional"))
    )
    (net (code "149") (name "unconnected-(J4-23-PadAA)") (class "Default")
      (node (ref "J4") (pin "AA") (pinfunction "23_AA") (pintype "bidirectional"))
    )
    (net (code "150") (name "unconnected-(J4-24-PadBB)") (class "Default")
      (node (ref "J4") (pin "BB") (pinfunction "24_BB") (pintype "bidirectional"))
    )
    (net (code "151") (name "unconnected-(J4-25-PadCC)") (class "Default")
      (node (ref "J4") (pin "CC") (pinfunction "25_CC") (pintype "bidirectional"))
    )
    (net (code "152") (name "unconnected-(J4-26-PadDD)") (class "Default")
      (node (ref "J4") (pin "DD") (pinfunction "26_DD") (pintype "bidirectional"))
    )
    (net (code "153") (name "unconnected-(J4-27-PadEE)") (class "Default")
      (node (ref "J4") (pin "EE") (pinfunction "27_EE") (pintype "bidirectional"))
    )
    (net (code "154") (name "unconnected-(J4-28-PadFF)") (class "Default")
      (node (ref "J4") (pin "FF") (pinfunction "28_FF") (pintype "bidirectional"))
    )
    (net (code "155") (name "unconnected-(J4-29-PadHH)") (class "Default")
      (node (ref "J4") (pin "HH") (pinfunction "29_HH") (pintype "bidirectional"))
    )
    (net (code "156") (name "unconnected-(J4-30-PadJJ)") (class "Default")
      (node (ref "J4") (pin "JJ") (pinfunction "30_JJ") (pintype "bidirectional"))
    )
    (net (code "157") (name "unconnected-(J4-31-PadKK)") (class "Default")
      (node (ref "J4") (pin "KK") (pinfunction "31_KK") (pintype "bidirectional"))
    )
    (net (code "158") (name "unconnected-(J4-32-PadLL)") (class "Default")
      (node (ref "J4") (pin "LL") (pinfunction "32_LL") (pintype "bidirectional"))
    )
    (net (code "159") (name "unconnected-(J4-33-PadMM)") (class "Default")
      (node (ref "J4") (pin "MM") (pinfunction "33_MM") (pintype "bidirectional"))
    )
    (net (code "160") (name "unconnected-(J4-34-PadNN)") (class "Default")
      (node (ref "J4") (pin "NN") (pinfunction "34_NN") (pintype "bidirectional"))
    )
    (net (code "161") (name "unconnected-(J4-35-PadPP)") (class "Default")
      (node (ref "J4") (pin "PP") (pinfunction "35_PP") (pintype "bidirectional"))
    )
    (net (code "162") (name "unconnected-(J4-36-PadRR)") (class "Default")
      (node (ref "J4") (pin "RR") (pinfunction "36_RR") (pintype "bidirectional"))
    )
    (net (code "163") (name "unconnected-(RN3-Pad8)") (class "Default")
      (node (ref "RN3") (pin "8") (pinfunction "8_8") (pintype "passive"))
    )
    (net (code "164") (name "unconnected-(RN3-Pad9)") (class "Default")
      (node (ref "RN3") (pin "9") (pinfunction "9_9") (pintype "passive"))
    )
    (net (code "165") (name "unconnected-(RN3-Pad10)") (class "Default")
      (node (ref "RN3") (pin "10") (pinfunction "10_10") (pintype "passive"))
    )
    (net (code "166") (name "unconnected-(RN3-Pad11)") (class "Default")
      (node (ref "RN3") (pin "11") (pinfunction "11_11") (pintype "passive"))
    )
    (net (code "167") (name "unconnected-(SV2-Pad6)") (class "Default")
      (node (ref "SV2") (pin "6") (pinfunction "6_6") (pintype "passive"))
    )
    (net (code "168") (name "unconnected-(SV2-Pad7)") (class "Default")
      (node (ref "SV2") (pin "7") (pinfunction "7_7") (pintype "passive"))
    )
    (net (code "169") (name "unconnected-(SV2-Pad8)") (class "Default")
      (node (ref "SV2") (pin "8") (pinfunction "8_8") (pintype "passive"))
    )
    (net (code "170") (name "unconnected-(TS_DISABLE-O-Pad1)") (class "Default")
      (node (ref "TS_DISABLE") (pin "1") (pinfunction "O_1") (pintype "passive"))
    )
    (net (code "171") (name "unconnected-(U2-GPA3-Pad24)") (class "Default")
      (node (ref "U2") (pin "24") (pinfunction "GPA3_24") (pintype "bidirectional"))
    )
    (net (code "172") (name "unconnected-(U2-GPA7-Pad28)") (class "Default")
      (node (ref "U2") (pin "28") (pinfunction "GPA7_28") (pintype "bidirectional"))
    )
    (net (code "173") (name "unconnected-(U2-GPB3-Pad4)") (class "Default")
      (node (ref "U2") (pin "4") (pinfunction "GPB3_4") (pintype "bidirectional"))
    )
    (net (code "174") (name "unconnected-(U2-GPB7-Pad8)") (class "Default")
      (node (ref "U2") (pin "8") (pinfunction "GPB7_8") (pintype "bidirectional"))
    )
    (net (code "175") (name "unconnected-(U2-INTA-Pad20)") (class "Default")
      (node (ref "U2") (pin "20") (pinfunction "INTA_20") (pintype "output"))
    )
    (net (code "176") (name "unconnected-(U2-INTB-Pad19)") (class "Default")
      (node (ref "U2") (pin "19") (pinfunction "INTB_19") (pintype "output"))
    )
    (net (code "177") (name "unconnected-(U7D-O-Pad11)") (class "Default")
      (node (ref "U7") (pin "11") (pinfunction "O_11") (pintype "open_collector"))
    )
    (net (code "178") (name "unconnected-(U10A-T1OUT-Pad14)") (class "Default")
      (node (ref "U10") (pin "14") (pinfunction "T1OUT_14") (pintype "output"))
    )
    (net (code "179") (name "~{BEMA0}") (class "Default")
      (node (ref "E1") (pin "18") (pinfunction "Y1_18") (pintype "tri_state"))
      (node (ref "E2") (pin "4") (pinfunction "A6_4") (pintype "input"))
      (node (ref "E2A") (pin "4") (pinfunction "A6_4") (pintype "input"))
      (node (ref "E5") (pin "4") (pinfunction "A6_4") (pintype "input"))
      (node (ref "E5A") (pin "4") (pinfunction "A6_4") (pintype "input"))
      (node (ref "E9") (pin "9") (pinfunction "C_9") (pintype "input"))
    )
    (net (code "180") (name "~{BEMA1}") (class "Default")
      (node (ref "E1") (pin "16") (pinfunction "Y2_16") (pintype "tri_state"))
      (node (ref "E2") (pin "5") (pinfunction "A5_5") (pintype "input"))
      (node (ref "E2A") (pin "5") (pinfunction "A5_5") (pintype "input"))
      (node (ref "E5") (pin "5") (pinfunction "A5_5") (pintype "input"))
      (node (ref "E5A") (pin "5") (pinfunction "A5_5") (pintype "input"))
      (node (ref "E9") (pin "10") (pinfunction "B_10") (pintype "input"))
    )
    (net (code "181") (name "~{BEMA2}") (class "Default")
      (node (ref "E1") (pin "14") (pinfunction "Y3_14") (pintype "tri_state"))
      (node (ref "E2") (pin "6") (pinfunction "A4_6") (pintype "input"))
      (node (ref "E2A") (pin "6") (pinfunction "A4_6") (pintype "input"))
      (node (ref "E5") (pin "6") (pinfunction "A4_6") (pintype "input"))
      (node (ref "E5A") (pin "6") (pinfunction "A4_6") (pintype "input"))
      (node (ref "E9") (pin "11") (pinfunction "A_11") (pintype "input"))
    )
    (net (code "182") (name "~{BMA00}") (class "Default")
      (node (ref "E1") (pin "9") (pinfunction "Y1_9") (pintype "tri_state"))
      (node (ref "E2") (pin "7") (pinfunction "A3_7") (pintype "input"))
      (node (ref "E2A") (pin "7") (pinfunction "A3_7") (pintype "input"))
      (node (ref "E5") (pin "7") (pinfunction "A3_7") (pintype "input"))
      (node (ref "E5A") (pin "7") (pinfunction "A3_7") (pintype "input"))
    )
    (net (code "183") (name "~{BMA01}") (class "Default")
      (node (ref "E1") (pin "7") (pinfunction "Y2_7") (pintype "tri_state"))
      (node (ref "E2") (pin "8") (pinfunction "A2_8") (pintype "input"))
      (node (ref "E2A") (pin "8") (pinfunction "A2_8") (pintype "input"))
      (node (ref "E5") (pin "8") (pinfunction "A2_8") (pintype "input"))
      (node (ref "E5A") (pin "8") (pinfunction "A2_8") (pintype "input"))
    )
    (net (code "184") (name "~{BMA02}") (class "Default")
      (node (ref "E1") (pin "5") (pinfunction "Y3_5") (pintype "tri_state"))
      (node (ref "E2") (pin "9") (pinfunction "A1_9") (pintype "input"))
      (node (ref "E2A") (pin "9") (pinfunction "A1_9") (pintype "input"))
      (node (ref "E5") (pin "9") (pinfunction "A1_9") (pintype "input"))
      (node (ref "E5A") (pin "9") (pinfunction "A1_9") (pintype "input"))
    )
    (net (code "185") (name "~{BMA03}") (class "Default")
      (node (ref "E1") (pin "3") (pinfunction "Y4_3") (pintype "tri_state"))
      (node (ref "E2") (pin "10") (pinfunction "A0_10") (pintype "input"))
      (node (ref "E2A") (pin "10") (pinfunction "A0_10") (pintype "input"))
      (node (ref "E5") (pin "10") (pinfunction "A0_10") (pintype "input"))
      (node (ref "E5A") (pin "10") (pinfunction "A0_10") (pintype "input"))
    )
    (net (code "186") (name "~{BMA04}") (class "Default")
      (node (ref "E2") (pin "3") (pinfunction "A7_3") (pintype "input"))
      (node (ref "E2A") (pin "3") (pinfunction "A7_3") (pintype "input"))
      (node (ref "E5") (pin "3") (pinfunction "A7_3") (pintype "input"))
      (node (ref "E5A") (pin "3") (pinfunction "A7_3") (pintype "input"))
      (node (ref "E7") (pin "3") (pinfunction "Y4_3") (pintype "tri_state"))
    )
    (net (code "187") (name "~{BMA05}") (class "Default")
      (node (ref "E2") (pin "2") (pinfunction "A12_2") (pintype "input"))
      (node (ref "E2A") (pin "2") (pinfunction "A12_2") (pintype "input"))
      (node (ref "E5") (pin "2") (pinfunction "A12_2") (pintype "input"))
      (node (ref "E5A") (pin "2") (pinfunction "A12_2") (pintype "input"))
      (node (ref "E7") (pin "5") (pinfunction "Y3_5") (pintype "tri_state"))
    )
    (net (code "188") (name "~{BMA06}") (class "Default")
      (node (ref "E2") (pin "1") (pinfunction "A14_1") (pintype "input"))
      (node (ref "E2A") (pin "1") (pinfunction "A14_1") (pintype "input"))
      (node (ref "E5") (pin "1") (pinfunction "A14_1") (pintype "input"))
      (node (ref "E5A") (pin "1") (pinfunction "A14_1") (pintype "input"))
      (node (ref "E7") (pin "7") (pinfunction "Y2_7") (pintype "tri_state"))
    )
    (net (code "189") (name "~{BMA07}") (class "Default")
      (node (ref "E2") (pin "24") (pinfunction "A9_24") (pintype "input"))
      (node (ref "E2A") (pin "24") (pinfunction "A9_24") (pintype "input"))
      (node (ref "E5") (pin "24") (pinfunction "A9_24") (pintype "input"))
      (node (ref "E5A") (pin "24") (pinfunction "A9_24") (pintype "input"))
      (node (ref "E7") (pin "9") (pinfunction "Y1_9") (pintype "tri_state"))
    )
    (net (code "190") (name "~{BMA08}") (class "Default")
      (node (ref "E2") (pin "25") (pinfunction "A8_25") (pintype "input"))
      (node (ref "E2A") (pin "25") (pinfunction "A8_25") (pintype "input"))
      (node (ref "E5") (pin "25") (pinfunction "A8_25") (pintype "input"))
      (node (ref "E5A") (pin "25") (pinfunction "A8_25") (pintype "input"))
      (node (ref "E7") (pin "18") (pinfunction "Y1_18") (pintype "tri_state"))
    )
    (net (code "191") (name "~{BMA09}") (class "Default")
      (node (ref "E2") (pin "26") (pinfunction "A13_26") (pintype "input"))
      (node (ref "E2A") (pin "26") (pinfunction "A13_26") (pintype "input"))
      (node (ref "E5") (pin "26") (pinfunction "A13_26") (pintype "input"))
      (node (ref "E5A") (pin "26") (pinfunction "A13_26") (pintype "input"))
      (node (ref "E7") (pin "16") (pinfunction "Y2_16") (pintype "tri_state"))
    )
    (net (code "192") (name "~{BMA10}") (class "Default")
      (node (ref "E2") (pin "21") (pinfunction "A10_21") (pintype "input"))
      (node (ref "E2A") (pin "21") (pinfunction "A10_21") (pintype "input"))
      (node (ref "E5") (pin "21") (pinfunction "A10_21") (pintype "input"))
      (node (ref "E5A") (pin "21") (pinfunction "A10_21") (pintype "input"))
      (node (ref "E7") (pin "14") (pinfunction "Y3_14") (pintype "tri_state"))
    )
    (net (code "193") (name "~{BMA11}") (class "Default")
      (node (ref "E2") (pin "23") (pinfunction "A11_23") (pintype "input"))
      (node (ref "E2A") (pin "23") (pinfunction "A11_23") (pintype "input"))
      (node (ref "E5") (pin "23") (pinfunction "A11_23") (pintype "input"))
      (node (ref "E5A") (pin "23") (pinfunction "A11_23") (pintype "input"))
      (node (ref "E7") (pin "12") (pinfunction "Y4_12") (pintype "tri_state"))
    )
    (net (code "194") (name "~{BMD_DIR}") (class "Default")
      (node (ref "E6") (pin "14") (pinfunction "Y5_14") (pintype "tri_state"))
      (node (ref "E8") (pin "4") (pinfunction "I1_4") (pintype "input"))
    )
    (net (code "195") (name "~{BREAK_CYCLE}") (class "Default")
      (node (ref "J1") (pin "BL2") (pinfunction "1_BL2") (pintype "bidirectional"))
    )
    (net (code "196") (name "~{BRK_DATA}") (class "Default")
      (node (ref "J1") (pin "BK2") (pinfunction "1_BK2") (pintype "bidirectional"))
      (node (ref "U7") (pin "3") (pinfunction "O_3") (pintype "open_collector"))
    )
    (net (code "197") (name "~{BRK_IN_PROG}") (class "Default")
      (node (ref "J1") (pin "BE2") (pinfunction "1_BE2") (pintype "bidirectional"))
    )
    (net (code "198") (name "~{BSOURCE}") (class "Default")
      (node (ref "E6") (pin "17") (pinfunction "Y2_17") (pintype "tri_state"))
      (node (ref "E6") (pin "4") (pinfunction "A3_4") (pintype "input"))
    )
    (net (code "199") (name "~{BUS_STROBE}") (class "Default")
      (node (ref "J1") (pin "CK1") (pinfunction "1_CK1") (pintype "bidirectional"))
    )
    (net (code "200") (name "~{C0}") (class "Default")
      (node (ref "E14") (pin "35") (pinfunction "IO25_35") (pintype "bidirectional"))
      (node (ref "J1") (pin "CE1") (pinfunction "1_CE1") (pintype "bidirectional"))
    )
    (net (code "201") (name "~{C1}") (class "Default")
      (node (ref "E14") (pin "33") (pinfunction "IO23_33") (pintype "bidirectional"))
      (node (ref "J1") (pin "CH1") (pinfunction "1_CH1") (pintype "bidirectional"))
    )
    (net (code "202") (name "~{C2}") (class "Default")
      (node (ref "J1") (pin "CJ1") (pinfunction "1_CJ1") (pintype "bidirectional"))
    )
    (net (code "203") (name "~{CE_OK}") (class "Default")
      (node (ref "C22") (pin "2") (pinfunction "2_2") (pintype "passive"))
      (node (ref "E8") (pin "12") (pinfunction "O_12") (pintype "output"))
      (node (ref "Q3") (pin "3") (pinfunction "E_3") (pintype "passive"))
    )
    (net (code "204") (name "~{CE}") (class "Default")
      (node (ref "C22") (pin "1") (pinfunction "1_1") (pintype "passive"))
      (node (ref "E2") (pin "20") (pinfunction "~{CE}_20") (pintype "input"))
      (node (ref "E2A") (pin "20") (pinfunction "~{CS}_20") (pintype "input"))
      (node (ref "E5") (pin "20") (pinfunction "~{CE}_20") (pintype "input"))
      (node (ref "E5A") (pin "20") (pinfunction "~{CS}_20") (pintype "input"))
      (node (ref "Q3") (pin "1") (pinfunction "C_1") (pintype "passive"))
      (node (ref "R15") (pin "1") (pinfunction "1_1") (pintype "passive"))
    )
    (net (code "205") (name "~{CPMA_DISABLE}") (class "Default")
      (node (ref "E14") (pin "21") (pinfunction "IO14_21") (pintype "bidirectional"))
      (node (ref "J1") (pin "CU1") (pinfunction "1_CU1") (pintype "bidirectional"))
    )
    (net (code "206") (name "~{DATA00}") (class "Default")
      (node (ref "E14") (pin "61") (pinfunction "IO45_61") (pintype "bidirectional"))
      (node (ref "J1") (pin "AR1") (pinfunction "1_AR1") (pintype "bidirectional"))
      (node (ref "U3") (pin "3") (pinfunction "O_3") (pintype "open_collector"))
    )
    (net (code "207") (name "~{DATA01}") (class "Default")
      (node (ref "E14") (pin "60") (pinfunction "IO44_60") (pintype "bidirectional"))
      (node (ref "J1") (pin "AS1") (pinfunction "1_AS1") (pintype "bidirectional"))
      (node (ref "U3") (pin "6") (pinfunction "O_6") (pintype "open_collector"))
    )
    (net (code "208") (name "~{DATA02}") (class "Default")
      (node (ref "E14") (pin "58") (pinfunction "IO43_58") (pintype "bidirectional"))
      (node (ref "J1") (pin "AU1") (pinfunction "1_AU1") (pintype "bidirectional"))
      (node (ref "U3") (pin "11") (pinfunction "O_11") (pintype "open_collector"))
    )
    (net (code "209") (name "~{DATA03}") (class "Default")
      (node (ref "E14") (pin "57") (pinfunction "IO42_57") (pintype "bidirectional"))
      (node (ref "J1") (pin "AV1") (pinfunction "1_AV1") (pintype "bidirectional"))
      (node (ref "U3") (pin "8") (pinfunction "O_8") (pintype "open_collector"))
    )
    (net (code "210") (name "~{DATA04}") (class "Default")
      (node (ref "E14") (pin "46") (pinfunction "IO33_46") (pintype "bidirectional"))
      (node (ref "J1") (pin "BR1") (pinfunction "1_BR1") (pintype "bidirectional"))
      (node (ref "U4") (pin "3") (pinfunction "O_3") (pintype "open_collector"))
    )
    (net (code "211") (name "~{DATA05}") (class "Default")
      (node (ref "E14") (pin "45") (pinfunction "IO/PD2_45") (pintype "bidirectional"))
      (node (ref "J1") (pin "BS1") (pinfunction "1_BS1") (pintype "bidirectional"))
      (node (ref "U4") (pin "6") (pinfunction "O_6") (pintype "open_collector"))
    )
    (net (code "212") (name "~{DATA06}") (class "Default")
      (node (ref "E14") (pin "44") (pinfunction "IO31_44") (pintype "bidirectional"))
      (node (ref "J1") (pin "BU1") (pinfunction "1_BU1") (pintype "bidirectional"))
      (node (ref "U4") (pin "11") (pinfunction "O_11") (pintype "open_collector"))
    )
    (net (code "213") (name "~{DATA07}") (class "Default")
      (node (ref "E14") (pin "40") (pinfunction "IO29_40") (pintype "bidirectional"))
      (node (ref "J1") (pin "BV1") (pinfunction "1_BV1") (pintype "bidirectional"))
      (node (ref "U4") (pin "8") (pinfunction "O_8") (pintype "open_collector"))
    )
    (net (code "214") (name "~{DATA08}") (class "Default")
      (node (ref "E14") (pin "4") (pinfunction "IO1_4") (pintype "bidirectional"))
      (node (ref "J1") (pin "DR1") (pinfunction "1_DR1") (pintype "bidirectional"))
      (node (ref "U5") (pin "3") (pinfunction "O_3") (pintype "open_collector"))
    )
    (net (code "215") (name "~{DATA09}") (class "Default")
      (node (ref "E14") (pin "81") (pinfunction "IO/GCLK3_81") (pintype "bidirectional"))
      (node (ref "J1") (pin "DS1") (pinfunction "1_DS1") (pintype "bidirectional"))
      (node (ref "U5") (pin "6") (pinfunction "O_6") (pintype "open_collector"))
    )
    (net (code "216") (name "~{DATA10}") (class "Default")
      (node (ref "E14") (pin "80") (pinfunction "IO59_80") (pintype "bidirectional"))
      (node (ref "J1") (pin "DU1") (pinfunction "1_DU1") (pintype "bidirectional"))
      (node (ref "U5") (pin "11") (pinfunction "O_11") (pintype "open_collector"))
    )
    (net (code "217") (name "~{DATA11}") (class "Default")
      (node (ref "E14") (pin "77") (pinfunction "IO57_77") (pintype "bidirectional"))
      (node (ref "J1") (pin "DV1") (pinfunction "1_DV1") (pintype "bidirectional"))
      (node (ref "U5") (pin "8") (pinfunction "O_8") (pintype "open_collector"))
    )
    (net (code "218") (name "~{DISABLE}") (class "Default")
      (node (ref "E8") (pin "1") (pinfunction "I0_1") (pintype "input"))
      (node (ref "E8") (pin "10") (pinfunction "I1_10") (pintype "input"))
      (node (ref "E8") (pin "11") (pinfunction "I2_11") (pintype "input"))
      (node (ref "E8") (pin "2") (pinfunction "I1_2") (pintype "input"))
      (node (ref "E9") (pin "5") (pinfunction "Y_5") (pintype "output"))
    )
    (net (code "219") (name "~{D}") (class "Default")
      (node (ref "E14") (pin "11") (pinfunction "IO7_11") (pintype "bidirectional"))
      (node (ref "J1") (pin "DK2") (pinfunction "1_DK2") (pintype "bidirectional"))
    )
    (net (code "220") (name "~{EMA0}") (class "Default")
      (node (ref "E1") (pin "2") (pinfunction "A1_2") (pintype "input"))
      (node (ref "E14") (pin "70") (pinfunction "IO52_70") (pintype "bidirectional"))
      (node (ref "J1") (pin "AD2") (pinfunction "1_AD2") (pintype "bidirectional"))
    )
    (net (code "221") (name "~{EMA1}") (class "Default")
      (node (ref "E1") (pin "4") (pinfunction "A2_4") (pintype "input"))
      (node (ref "E14") (pin "69") (pinfunction "IO51_69") (pintype "bidirectional"))
      (node (ref "J1") (pin "AE2") (pinfunction "1_AE2") (pintype "bidirectional"))
    )
    (net (code "222") (name "~{EMA2}") (class "Default")
      (node (ref "E1") (pin "6") (pinfunction "A3_6") (pintype "input"))
      (node (ref "E14") (pin "68") (pinfunction "IO50_68") (pintype "bidirectional"))
      (node (ref "J1") (pin "AH2") (pinfunction "1_AH2") (pintype "bidirectional"))
    )
    (net (code "223") (name "~{E}") (class "Default")
      (node (ref "J1") (pin "DL2") (pinfunction "1_DL2") (pintype "bidirectional"))
    )
    (net (code "224") (name "~{F_SET}") (class "Default")
      (node (ref "E14") (pin "5") (pinfunction "IO2_5") (pintype "bidirectional"))
      (node (ref "J1") (pin "DP2") (pinfunction "1_DP2") (pintype "bidirectional"))
    )
    (net (code "225") (name "~{F}") (class "Default")
      (node (ref "E14") (pin "15") (pinfunction "IO9_15") (pintype "bidirectional"))
      (node (ref "J1") (pin "DJ2") (pinfunction "1_DJ2") (pintype "bidirectional"))
    )
    (net (code "226") (name "~{IND1}") (class "Default")
      (node (ref "E14") (pin "20") (pinfunction "IO13_20") (pintype "bidirectional"))
      (node (ref "J1") (pin "CU2") (pinfunction "1_CU2") (pintype "bidirectional"))
    )
    (net (code "227") (name "~{IND2}") (class "Default")
      (node (ref "E14") (pin "18") (pinfunction "IO12_18") (pintype "bidirectional"))
      (node (ref "J1") (pin "CV2") (pinfunction "1_CV2") (pintype "bidirectional"))
    )
    (net (code "228") (name "~{INTERNAL_IO}") (class "Default")
      (node (ref "E14") (pin "28") (pinfunction "IO19_28") (pintype "bidirectional"))
      (node (ref "J1") (pin "CL1") (pinfunction "1_CL1") (pintype "bidirectional"))
    )
    (net (code "229") (name "~{INT_IN_PROG}") (class "Default")
      (node (ref "E14") (pin "48") (pinfunction "IO34_48") (pintype "bidirectional"))
      (node (ref "J1") (pin "BP2") (pinfunction "1_BP2") (pintype "bidirectional"))
    )
    (net (code "230") (name "~{INT_RQST}") (class "Default")
      (node (ref "E14") (pin "25") (pinfunction "IO17_25") (pintype "bidirectional"))
      (node (ref "J1") (pin "CP1") (pinfunction "1_CP1") (pintype "bidirectional"))
    )
    (net (code "231") (name "~{IO_PAUSE}") (class "Default")
      (node (ref "E14") (pin "36") (pinfunction "IO26_36") (pintype "bidirectional"))
      (node (ref "J1") (pin "CD1") (pinfunction "1_CD1") (pintype "bidirectional"))
    )
    (net (code "232") (name "~{IR00}") (class "Default")
      (node (ref "E14") (pin "17") (pinfunction "IO11_17") (pintype "bidirectional"))
      (node (ref "J1") (pin "DD2") (pinfunction "1_DD2") (pintype "bidirectional"))
    )
    (net (code "233") (name "~{IR01}") (class "Default")
      (node (ref "E14") (pin "16") (pinfunction "IO10_16") (pintype "bidirectional"))
      (node (ref "J1") (pin "DE2") (pinfunction "1_DE2") (pintype "bidirectional"))
    )
    (net (code "234") (name "~{IR2}") (class "Default")
      (node (ref "J1") (pin "DH2") (pinfunction "1_DH2") (pintype "bidirectional"))
    )
    (net (code "235") (name "~{KEY_CTL}") (class "Default")
      (node (ref "E14") (pin "79") (pinfunction "IO58_79") (pintype "bidirectional"))
      (node (ref "J1") (pin "DU2") (pinfunction "1_DU2") (pintype "bidirectional"))
      (node (ref "U6") (pin "11") (pinfunction "O_11") (pintype "open_collector"))
    )
    (net (code "236") (name "~{LA_ENABLE}") (class "Default")
      (node (ref "J1") (pin "BM2") (pinfunction "1_BM2") (pintype "bidirectional"))
      (node (ref "U6") (pin "6") (pinfunction "O_6") (pintype "open_collector"))
    )
    (net (code "237") (name "~{LINK_DATA}") (class "Default")
      (node (ref "J1") (pin "CR2") (pinfunction "1_CR2") (pintype "bidirectional"))
    )
    (net (code "238") (name "~{LINK_LOAD}") (class "Default")
      (node (ref "J1") (pin "CS2") (pinfunction "1_CS2") (pintype "bidirectional"))
    )
    (net (code "239") (name "~{LINK}") (class "Default")
      (node (ref "J1") (pin "AV2") (pinfunction "1_AV2") (pintype "bidirectional"))
    )
    (net (code "240") (name "~{LOAD_CONT}") (class "Default")
      (node (ref "E14") (pin "54") (pinfunction "IO39_54") (pintype "bidirectional"))
      (node (ref "J1") (pin "BH2") (pinfunction "1_BH2") (pintype "bidirectional"))
    )
    (net (code "241") (name "~{MA00}") (class "Default")
      (node (ref "E1") (pin "11") (pinfunction "A1_11") (pintype "input"))
      (node (ref "J1") (pin "AD1") (pinfunction "1_AD1") (pintype "bidirectional"))
    )
    (net (code "242") (name "~{MA01}") (class "Default")
      (node (ref "E1") (pin "13") (pinfunction "A2_13") (pintype "input"))
      (node (ref "J1") (pin "AE1") (pinfunction "1_AE1") (pintype "bidirectional"))
    )
    (net (code "243") (name "~{MA02}") (class "Default")
      (node (ref "E1") (pin "15") (pinfunction "A3_15") (pintype "input"))
      (node (ref "J1") (pin "AH1") (pinfunction "1_AH1") (pintype "bidirectional"))
    )
    (net (code "244") (name "~{MA03}") (class "Default")
      (node (ref "E1") (pin "17") (pinfunction "A4_17") (pintype "input"))
      (node (ref "J1") (pin "AJ1") (pinfunction "1_AJ1") (pintype "bidirectional"))
    )
    (net (code "245") (name "~{MA04}") (class "Default")
      (node (ref "E7") (pin "17") (pinfunction "A4_17") (pintype "input"))
      (node (ref "J1") (pin "BD1") (pinfunction "1_BD1") (pintype "bidirectional"))
    )
    (net (code "246") (name "~{MA05}") (class "Default")
      (node (ref "E7") (pin "15") (pinfunction "A3_15") (pintype "input"))
      (node (ref "J1") (pin "BE1") (pinfunction "1_BE1") (pintype "bidirectional"))
    )
    (net (code "247") (name "~{MA06}") (class "Default")
      (node (ref "E7") (pin "13") (pinfunction "A2_13") (pintype "input"))
      (node (ref "J1") (pin "BH1") (pinfunction "1_BH1") (pintype "bidirectional"))
    )
    (net (code "248") (name "~{MA07}") (class "Default")
      (node (ref "E7") (pin "11") (pinfunction "A1_11") (pintype "input"))
      (node (ref "J1") (pin "BJ1") (pinfunction "1_BJ1") (pintype "bidirectional"))
    )
    (net (code "249") (name "~{MA08}") (class "Default")
      (node (ref "E7") (pin "2") (pinfunction "A1_2") (pintype "input"))
      (node (ref "J1") (pin "DD1") (pinfunction "1_DD1") (pintype "bidirectional"))
    )
    (net (code "250") (name "~{MA09}") (class "Default")
      (node (ref "E7") (pin "4") (pinfunction "A2_4") (pintype "input"))
      (node (ref "J1") (pin "DE1") (pinfunction "1_DE1") (pintype "bidirectional"))
    )
    (net (code "251") (name "~{MA10}") (class "Default")
      (node (ref "E7") (pin "6") (pinfunction "A3_6") (pintype "input"))
      (node (ref "J1") (pin "DH1") (pinfunction "1_DH1") (pintype "bidirectional"))
    )
    (net (code "252") (name "~{MA11}") (class "Default")
      (node (ref "E7") (pin "8") (pinfunction "A4_8") (pintype "input"))
      (node (ref "J1") (pin "DJ1") (pinfunction "1_DJ1") (pintype "bidirectional"))
    )
    (net (code "253") (name "~{MD00}") (class "Default")
      (node (ref "E14") (pin "67") (pinfunction "IO49_67") (pintype "bidirectional"))
      (node (ref "E3") (pin "1") (pinfunction "I0_1") (pintype "input"))
      (node (ref "E3") (pin "6") (pinfunction "O_6") (pintype "open_collector"))
      (node (ref "J1") (pin "AK1") (pinfunction "1_AK1") (pintype "bidirectional"))
    )
    (net (code "254") (name "~{MD01}") (class "Default")
      (node (ref "E14") (pin "65") (pinfunction "IO48_65") (pintype "bidirectional"))
      (node (ref "E3") (pin "12") (pinfunction "I0_12") (pintype "input"))
      (node (ref "E3") (pin "8") (pinfunction "O_8") (pintype "open_collector"))
      (node (ref "J1") (pin "AL1") (pinfunction "1_AL1") (pintype "bidirectional"))
    )
    (net (code "255") (name "~{MD02}") (class "Default")
      (node (ref "E14") (pin "64") (pinfunction "IO47_64") (pintype "bidirectional"))
      (node (ref "E4") (pin "1") (pinfunction "I0_1") (pintype "input"))
      (node (ref "E4") (pin "6") (pinfunction "O_6") (pintype "open_collector"))
      (node (ref "J1") (pin "AM1") (pinfunction "1_AM1") (pintype "bidirectional"))
    )
    (net (code "256") (name "~{MD03}") (class "Default")
      (node (ref "E14") (pin "63") (pinfunction "IO46_63") (pintype "bidirectional"))
      (node (ref "E4") (pin "12") (pinfunction "I0_12") (pintype "input"))
      (node (ref "E4") (pin "8") (pinfunction "O_8") (pintype "open_collector"))
      (node (ref "J1") (pin "AP1") (pinfunction "1_AP1") (pintype "bidirectional"))
    )
    (net (code "257") (name "~{MD04}") (class "Default")
      (node (ref "E10") (pin "1") (pinfunction "I0_1") (pintype "input"))
      (node (ref "E10") (pin "6") (pinfunction "O_6") (pintype "open_collector"))
      (node (ref "E14") (pin "52") (pinfunction "IO38_52") (pintype "bidirectional"))
      (node (ref "J1") (pin "BK1") (pinfunction "1_BK1") (pintype "bidirectional"))
    )
    (net (code "258") (name "~{MD05}") (class "Default")
      (node (ref "E10") (pin "12") (pinfunction "I0_12") (pintype "input"))
      (node (ref "E10") (pin "8") (pinfunction "O_8") (pintype "open_collector"))
      (node (ref "E14") (pin "51") (pinfunction "IO37_51") (pintype "bidirectional"))
      (node (ref "J1") (pin "BL1") (pinfunction "1_BL1") (pintype "bidirectional"))
    )
    (net (code "259") (name "~{MD06}") (class "Default")
      (node (ref "E11") (pin "1") (pinfunction "I0_1") (pintype "input"))
      (node (ref "E11") (pin "6") (pinfunction "O_6") (pintype "open_collector"))
      (node (ref "E14") (pin "50") (pinfunction "IO36_50") (pintype "bidirectional"))
      (node (ref "J1") (pin "BM1") (pinfunction "1_BM1") (pintype "bidirectional"))
    )
    (net (code "260") (name "~{MD07}") (class "Default")
      (node (ref "E11") (pin "12") (pinfunction "I0_12") (pintype "input"))
      (node (ref "E11") (pin "8") (pinfunction "O_8") (pintype "open_collector"))
      (node (ref "E14") (pin "49") (pinfunction "IO35_49") (pintype "bidirectional"))
      (node (ref "J1") (pin "BP1") (pinfunction "1_BP1") (pintype "bidirectional"))
    )
    (net (code "261") (name "~{MD08}") (class "Default")
      (node (ref "E12") (pin "1") (pinfunction "I0_1") (pintype "input"))
      (node (ref "E12") (pin "6") (pinfunction "O_6") (pintype "open_collector"))
      (node (ref "E14") (pin "12") (pinfunction "IO/PD1_12") (pintype "bidirectional"))
      (node (ref "J1") (pin "DK1") (pinfunction "1_DK1") (pintype "bidirectional"))
    )
    (net (code "262") (name "~{MD09}") (class "Default")
      (node (ref "E12") (pin "12") (pinfunction "I0_12") (pintype "input"))
      (node (ref "E12") (pin "8") (pinfunction "O_8") (pintype "open_collector"))
      (node (ref "E14") (pin "10") (pinfunction "IO6_10") (pintype "bidirectional"))
      (node (ref "J1") (pin "DL1") (pinfunction "1_DL1") (pintype "bidirectional"))
    )
    (net (code "263") (name "~{MD10}") (class "Default")
      (node (ref "E13") (pin "1") (pinfunction "I0_1") (pintype "input"))
      (node (ref "E13") (pin "6") (pinfunction "O_6") (pintype "open_collector"))
      (node (ref "E14") (pin "9") (pinfunction "IO5_9") (pintype "bidirectional"))
      (node (ref "J1") (pin "DM1") (pinfunction "1_DM1") (pintype "bidirectional"))
    )
    (net (code "264") (name "~{MD11}") (class "Default")
      (node (ref "E13") (pin "12") (pinfunction "I0_12") (pintype "input"))
      (node (ref "E13") (pin "8") (pinfunction "O_8") (pintype "open_collector"))
      (node (ref "E14") (pin "6") (pinfunction "IO3_6") (pintype "bidirectional"))
      (node (ref "J1") (pin "DP1") (pinfunction "1_DP1") (pintype "bidirectional"))
    )
    (net (code "265") (name "~{MD_DIR}") (class "Default")
      (node (ref "E6") (pin "5") (pinfunction "A4_5") (pintype "input"))
      (node (ref "J1") (pin "AK2") (pinfunction "1_AK2") (pintype "bidirectional"))
      (node (ref "U7") (pin "6") (pinfunction "O_6") (pintype "open_collector"))
    )
    (net (code "266") (name "~{MEM_START}") (class "Default")
      (node (ref "J1") (pin "AJ2") (pinfunction "1_AJ2") (pintype "bidirectional"))
      (node (ref "U6") (pin "3") (pinfunction "O_3") (pintype "open_collector"))
    )
    (net (code "267") (name "~{MS_DISABLE}") (class "Default")
      (node (ref "J1") (pin "CV1") (pinfunction "1_CV1") (pintype "bidirectional"))
      (node (ref "U6") (pin "8") (pinfunction "O_8") (pintype "open_collector"))
    )
    (net (code "268") (name "~{NOT_LAST_TR}") (class "Default")
      (node (ref "J1") (pin "CM1") (pinfunction "1_CM1") (pintype "bidirectional"))
    )
    (net (code "269") (name "~{NTS_STALL}") (class "Default")
      (node (ref "J1") (pin "BR2") (pinfunction "1_BR2") (pintype "bidirectional"))
    )
    (net (code "270") (name "~{OE}") (class "Default")
      (node (ref "E2") (pin "22") (pinfunction "~{OE}_22") (pintype "input"))
      (node (ref "E2A") (pin "22") (pinfunction "~{OE}_22") (pintype "input"))
      (node (ref "E5") (pin "22") (pinfunction "~{OE}_22") (pintype "input"))
      (node (ref "E5A") (pin "22") (pinfunction "~{OE}_22") (pintype "input"))
      (node (ref "E6") (pin "8") (pinfunction "A7_8") (pintype "input"))
      (node (ref "E8") (pin "8") (pinfunction "O_8") (pintype "output"))
    )
    (net (code "271") (name "~{OVERFLOW}") (class "Default")
      (node (ref "J1") (pin "BJ2") (pinfunction "1_BJ2") (pintype "bidirectional"))
    )
    (net (code "272") (name "~{RESET}") (class "Default")
      (node (ref "C11") (pin "1") (pinfunction "1_1") (pintype "passive"))
      (node (ref "D1") (pin "A") (pinfunction "A_A") (pintype "passive"))
      (node (ref "J3") (pin "5") (pinfunction "5_5") (pintype "passive"))
      (node (ref "R19") (pin "1") (pinfunction "1_1") (pintype "passive"))
      (node (ref "U1") (pin "1") (pinfunction "PC6(/RESET)_1") (pintype "bidirectional"))
    )
    (net (code "273") (name "~{ROM_ADDR}") (class "Default")
      (node (ref "E6") (pin "9") (pinfunction "A8_9") (pintype "input"))
      (node (ref "J1") (pin "AU2") (pinfunction "1_AU2") (pintype "bidirectional"))
    )
    (net (code "274") (name "~{RUN}") (class "Default")
      (node (ref "E14") (pin "41") (pinfunction "IO30_41") (pintype "bidirectional"))
      (node (ref "J1") (pin "BU2") (pinfunction "1_BU2") (pintype "bidirectional"))
      (node (ref "R2") (pin "2") (pinfunction "2_2") (pintype "passive"))
    )
    (net (code "275") (name "~{SKIP}") (class "Default")
      (node (ref "E14") (pin "22") (pinfunction "IO15_22") (pintype "bidirectional"))
      (node (ref "J1") (pin "CS1") (pinfunction "1_CS1") (pintype "bidirectional"))
    )
    (net (code "276") (name "~{STOP}") (class "Default")
      (node (ref "J1") (pin "DS2") (pinfunction "1_DS2") (pintype "bidirectional"))
      (node (ref "U7") (pin "8") (pinfunction "O_8") (pintype "open_collector"))
    )
    (net (code "277") (name "~{TP4}") (class "Default")
      (node (ref "E6") (pin "18") (pinfunction "Y1_18") (pintype "tri_state"))
      (node (ref "E8") (pin "13") (pinfunction "I2_13") (pintype "input"))
    )
    (net (code "278") (name "~{TS1}") (class "Default")
      (node (ref "E14") (pin "29") (pinfunction "IO20_29") (pintype "bidirectional"))
      (node (ref "J1") (pin "CK2") (pinfunction "1_CK2") (pintype "bidirectional"))
    )
    (net (code "279") (name "~{TS2}") (class "Default")
      (node (ref "J1") (pin "CL2") (pinfunction "1_CL2") (pintype "bidirectional"))
    )
    (net (code "280") (name "~{TS3}") (class "Default")
      (node (ref "E14") (pin "27") (pinfunction "IO18_27") (pintype "bidirectional"))
      (node (ref "J1") (pin "CM2") (pinfunction "1_CM2") (pintype "bidirectional"))
    )
    (net (code "281") (name "~{TS4}") (class "Default")
      (node (ref "J1") (pin "CP2") (pinfunction "1_CP2") (pintype "bidirectional"))
      (node (ref "U8") (pin "13") (pinfunction "I2_13") (pintype "input"))
    )
    (net (code "282") (name "~{USER_MODE}") (class "Default")
      (node (ref "E14") (pin "8") (pinfunction "IO4_8") (pintype "bidirectional"))
      (node (ref "J1") (pin "DM2") (pinfunction "1_DM2") (pintype "bidirectional"))
    )
    (net (code "283") (name "~{WE}") (class "Default")
      (node (ref "E2") (pin "27") (pinfunction "~{WE}_27") (pintype "input"))
      (node (ref "E2A") (pin "27") (pinfunction "~{WE}_27") (pintype "input"))
      (node (ref "E5") (pin "27") (pinfunction "~{WE}_27") (pintype "input"))
      (node (ref "E5A") (pin "27") (pinfunction "~{WE}_27") (pintype "input"))
      (node (ref "E6") (pin "7") (pinfunction "A6_7") (pintype "input"))
      (node (ref "E8") (pin "6") (pinfunction "O_6") (pintype "output"))
    )
    (net (code "284") (name "~{W_KEY_CONTROL}") (class "Default")
      (node (ref "U1") (pin "13") (pinfunction "PD7(AIN1)_13") (pintype "bidirectional"))
      (node (ref "U6") (pin "12") (pinfunction "I0_12") (pintype "input"))
    )
    (net (code "285") (name "~{W_LA_ENABLE}") (class "Default")
      (node (ref "U1") (pin "11") (pinfunction "PD5(T1)_11") (pintype "bidirectional"))
      (node (ref "U6") (pin "4") (pinfunction "I0_4") (pintype "input"))
    )
    (net (code "286") (name "~{W_MEM_START}") (class "Default")
      (node (ref "R7") (pin "2") (pinfunction "2_2") (pintype "passive"))
      (node (ref "U1") (pin "25") (pinfunction "PC2(ADC2)_25") (pintype "bidirectional"))
      (node (ref "U6") (pin "1") (pinfunction "I0_1") (pintype "input"))
      (node (ref "U6") (pin "2") (pinfunction "I1_2") (pintype "input"))
    )
    (net (code "287") (name "~{W_MS_IR_DISABLE}") (class "Default")
      (node (ref "U1") (pin "12") (pinfunction "PD6(AIN0)_12") (pintype "bidirectional"))
      (node (ref "U6") (pin "9") (pinfunction "I0_9") (pintype "input"))
    )
  )
)
